# display_driver_rev_B.net
KiCad netlist of a schematic drawn in EAGLE
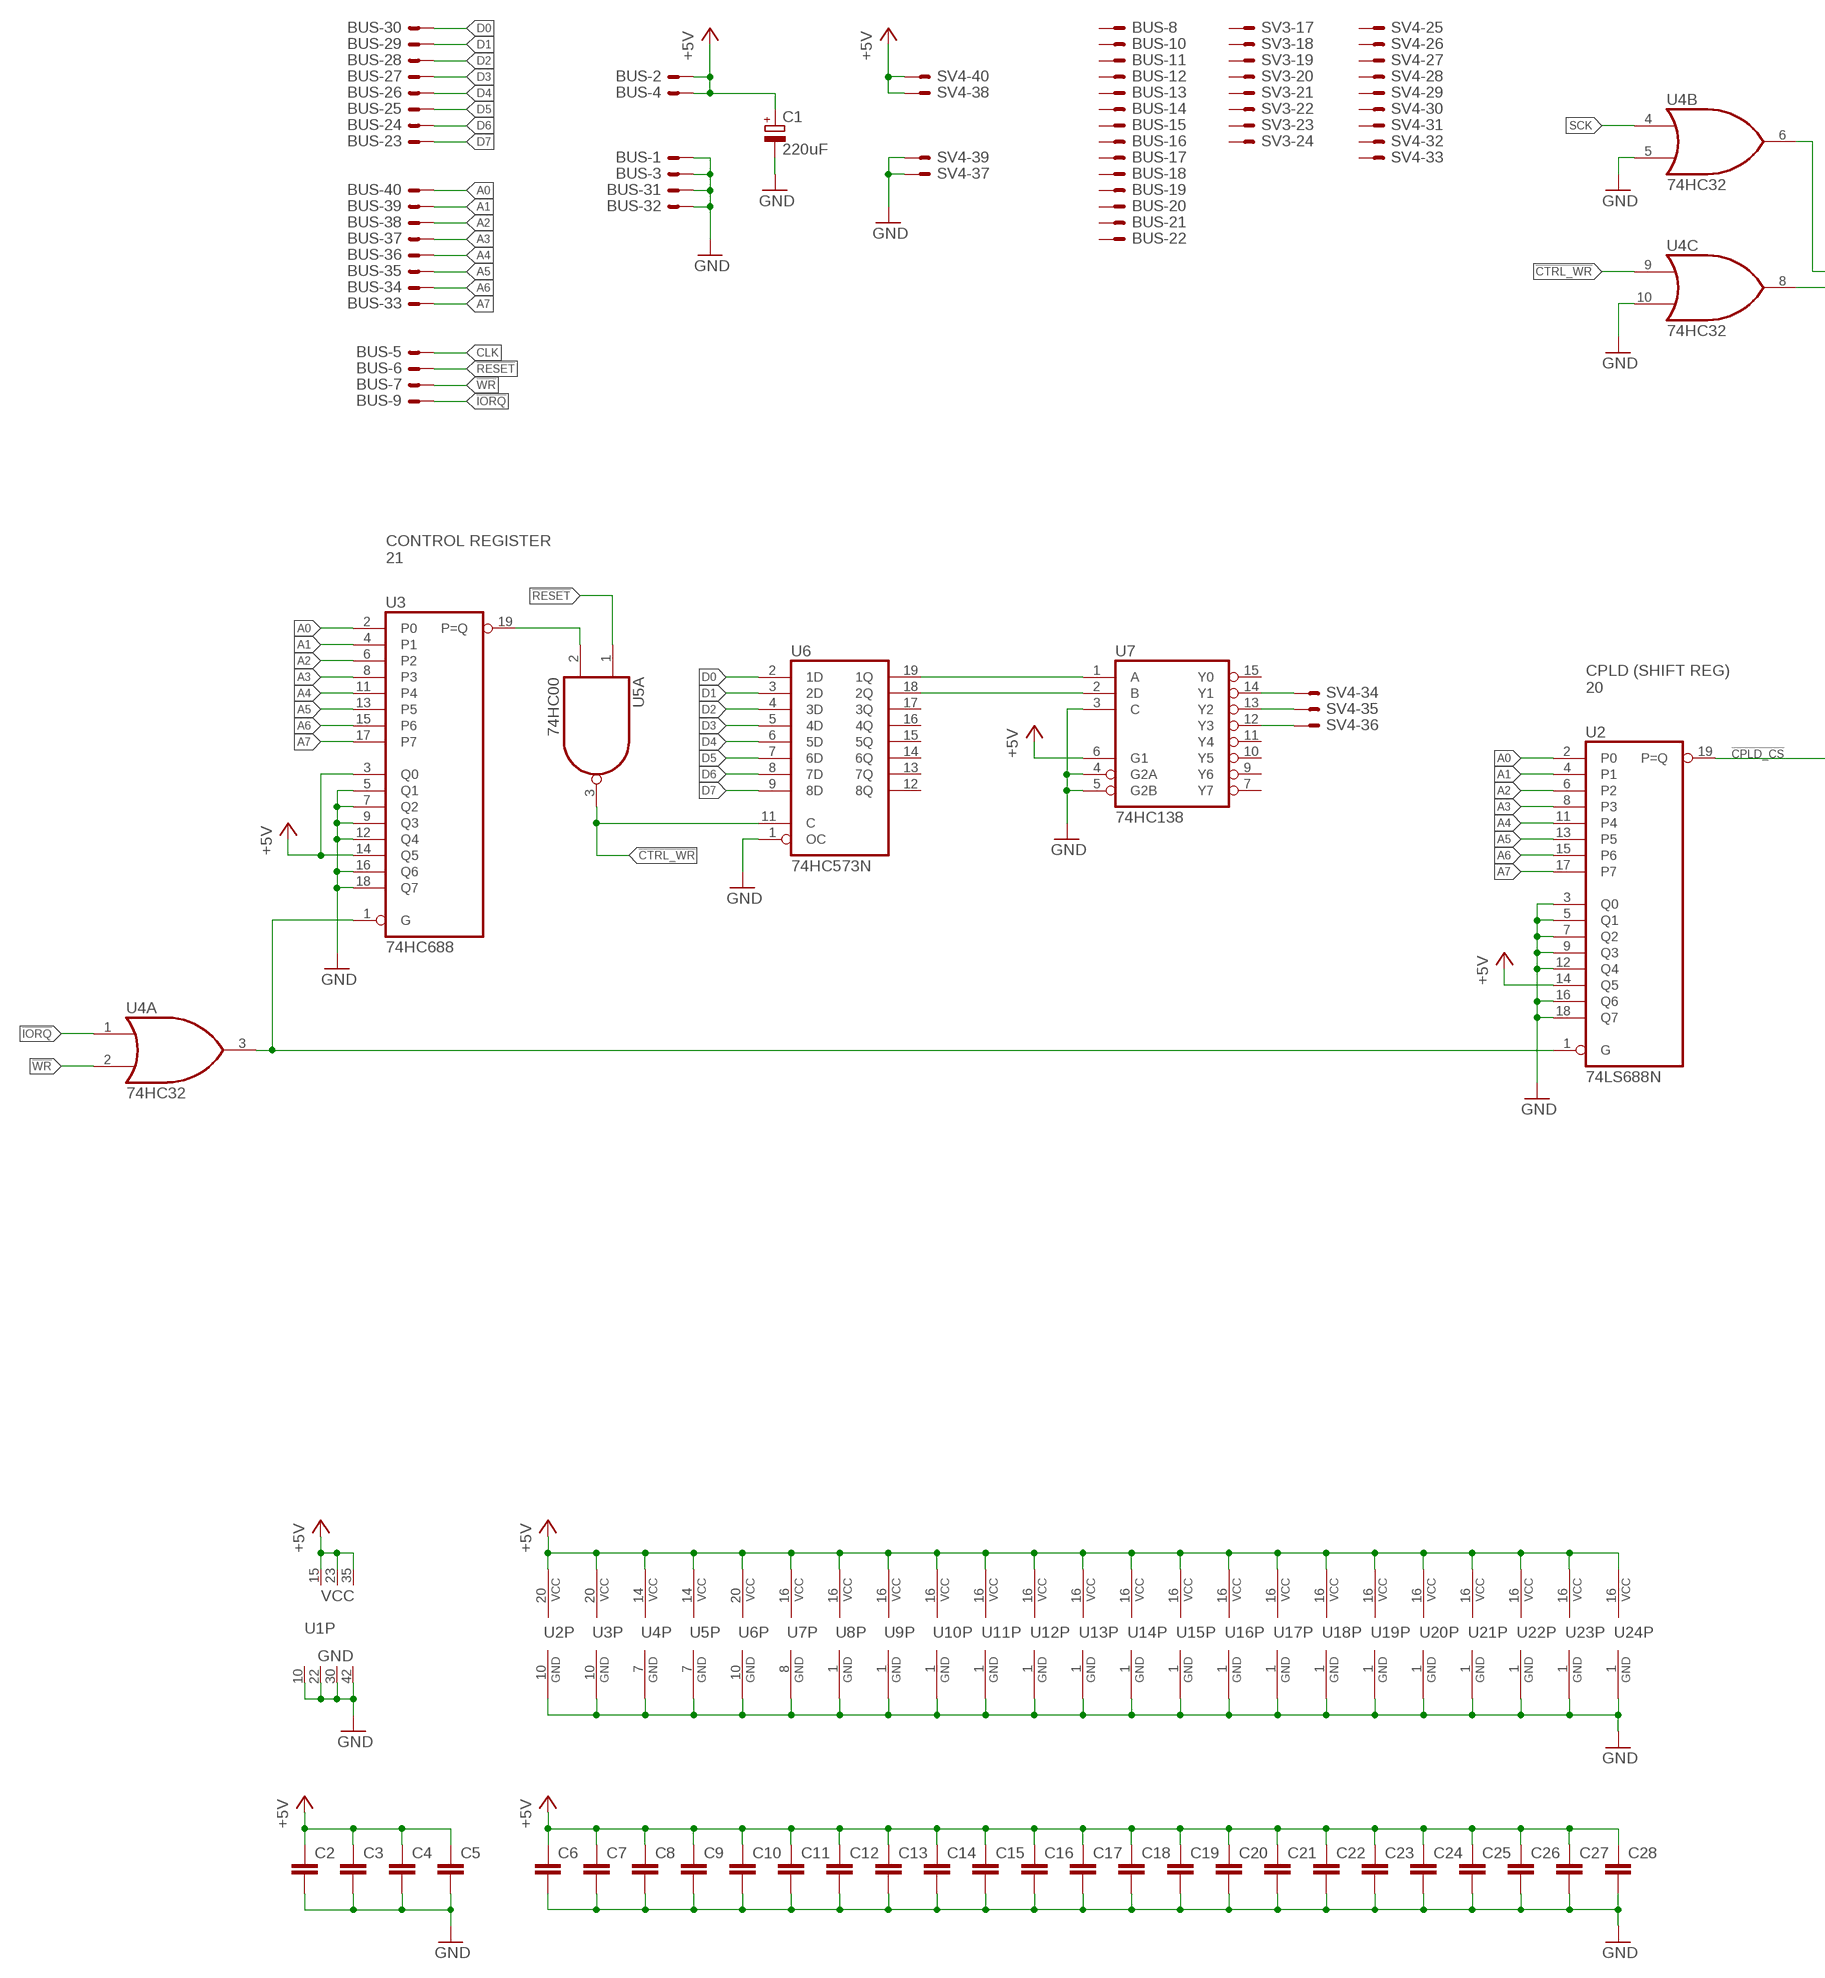
[diagram p0: schematic, sheet 1, part 1 of 2]
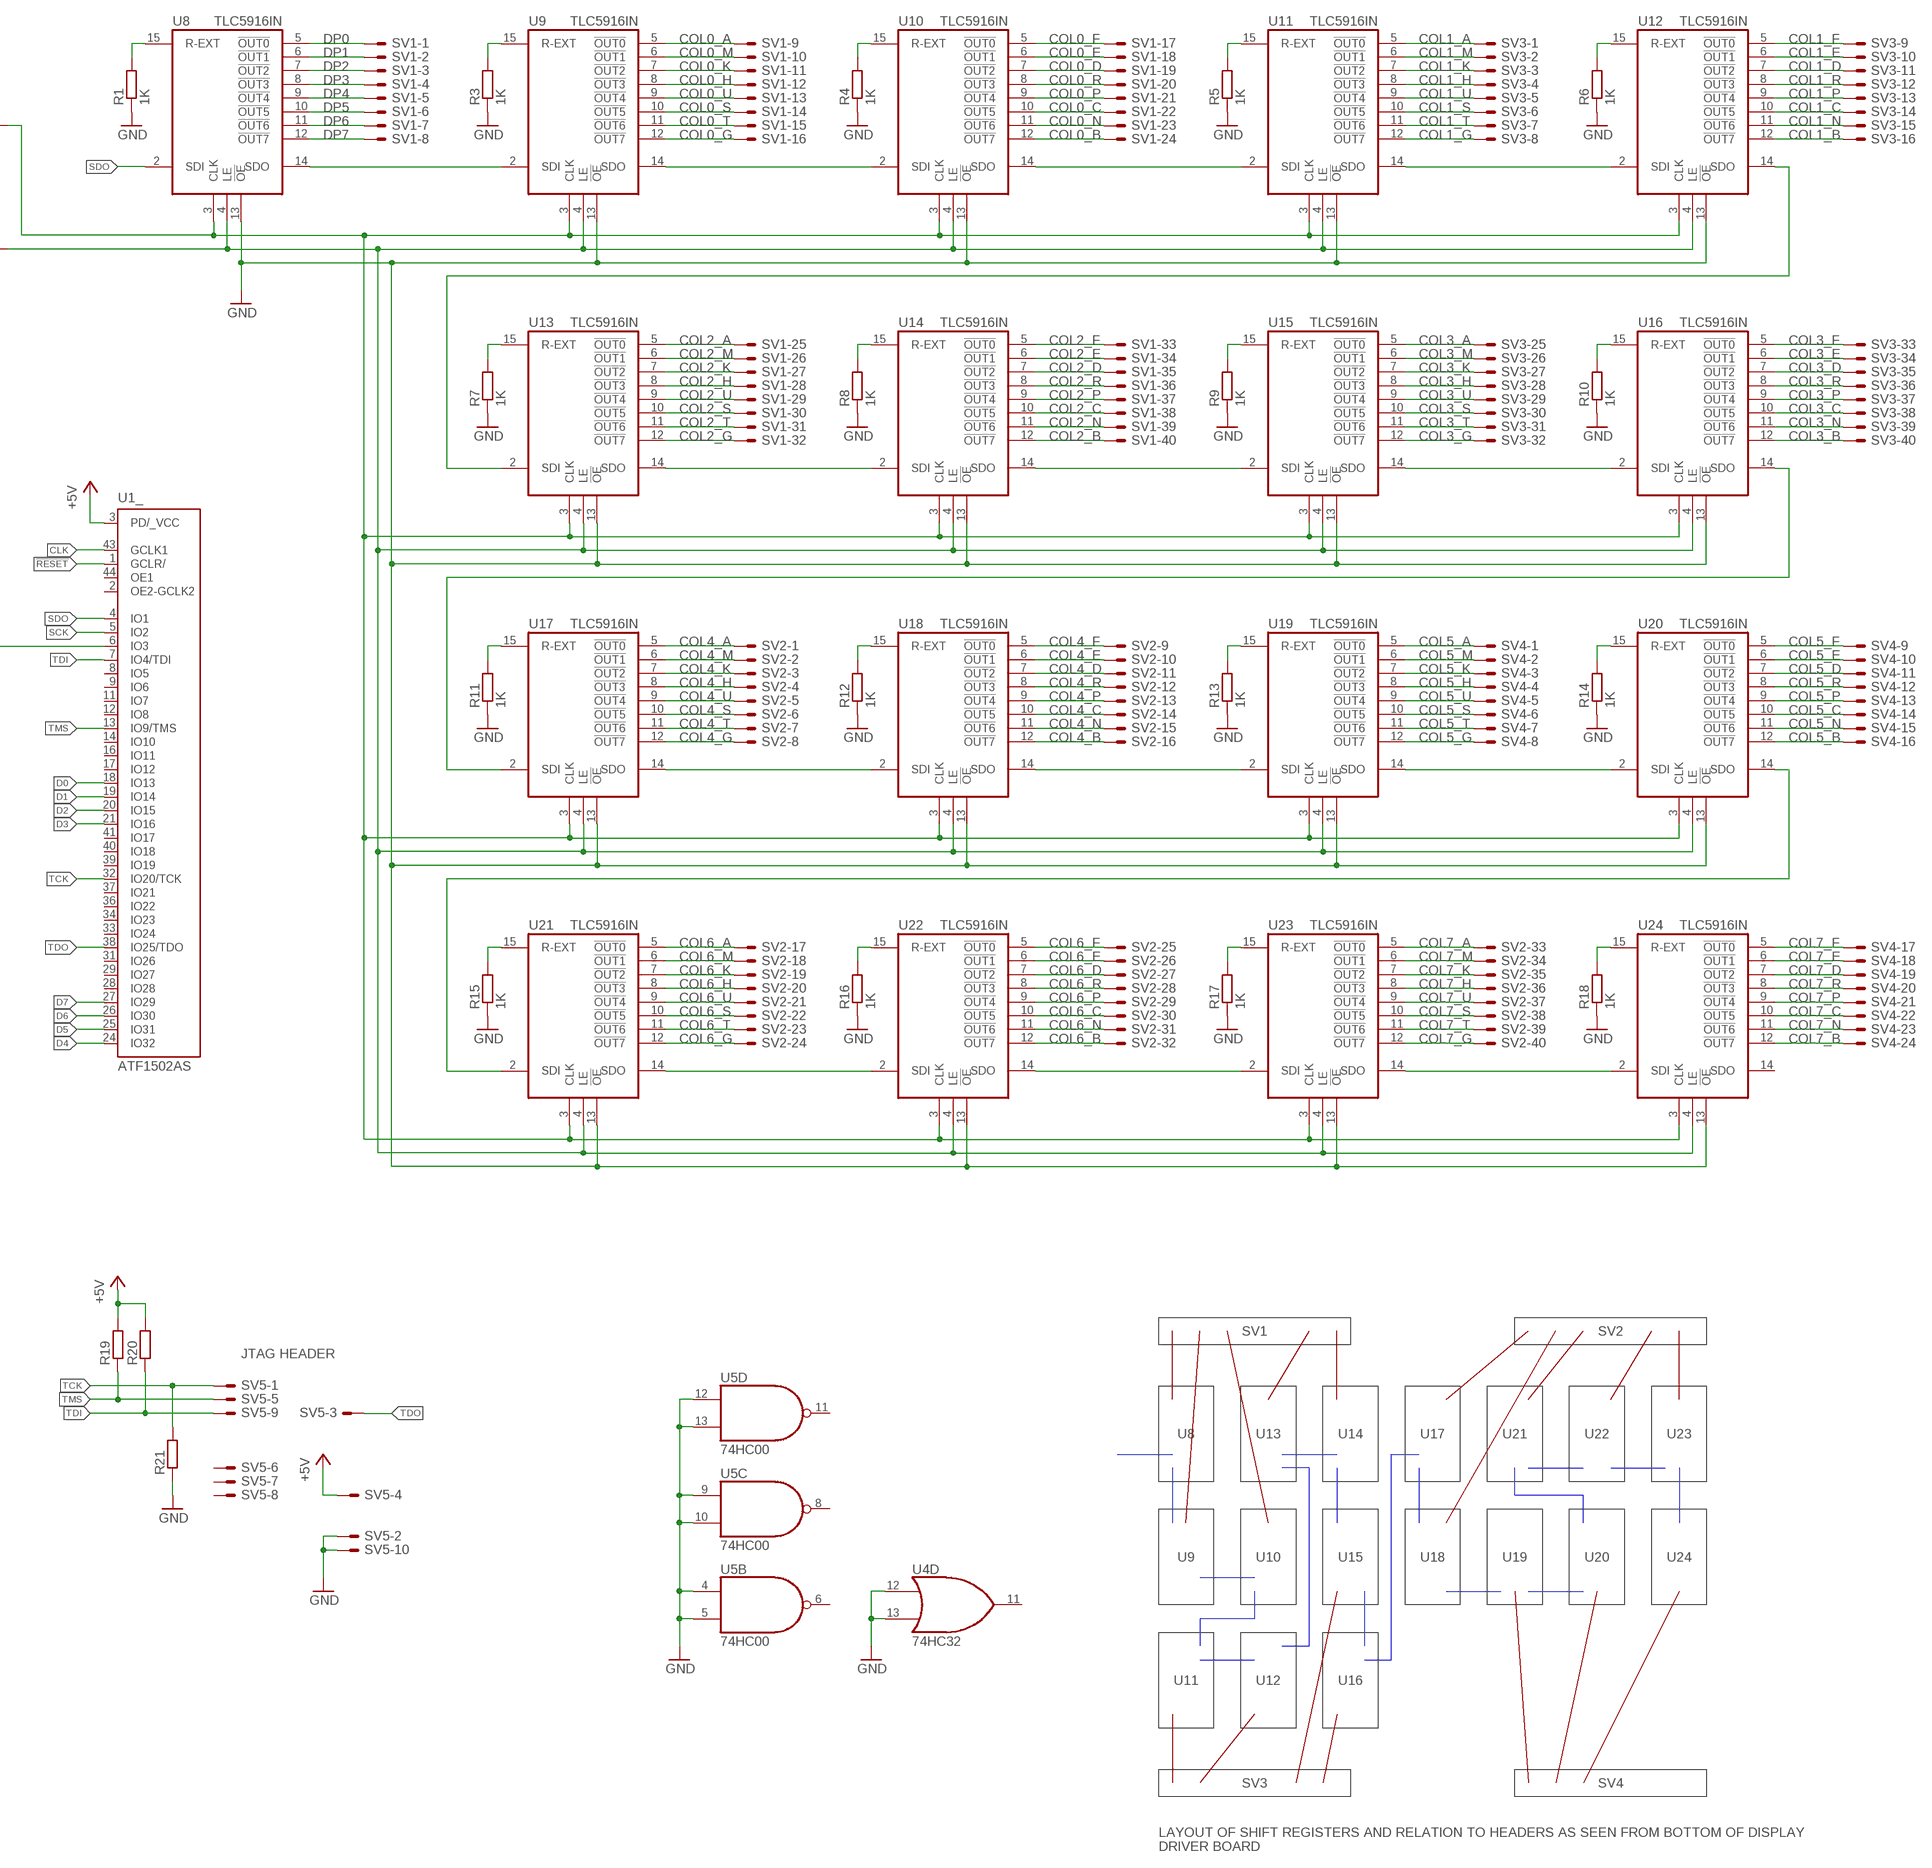
[diagram p1: schematic, sheet 1, part 2 of 2]

(export (version "E")
  (design (tool "Eeschema 10.0.6"))
  (components
    (comp (ref "BUS")
      (value "ML40E")
      (footprint "eagle-import:ML40")
      (libsource (lib "eagle-import") (part "ML40E"))
    )
    (comp (ref "C1")
      (value "220uF")
      (footprint "eagle-import:E3,5-8")
      (libsource (lib "eagle-import") (part "CPOL-EUE3.5-8"))
    )
    (comp (ref "C2")
      (value "C-EU050-025X075")
      (footprint "eagle-import:C050-025X075")
      (libsource (lib "eagle-import") (part "C-EU050-025X075"))
    )
    (comp (ref "C3")
      (value "C-EU050-025X075")
      (footprint "eagle-import:C050-025X075")
      (libsource (lib "eagle-import") (part "C-EU050-025X075"))
    )
    (comp (ref "C4")
      (value "C-EU050-025X075")
      (footprint "eagle-import:C050-025X075")
      (libsource (lib "eagle-import") (part "C-EU050-025X075"))
    )
    (comp (ref "C5")
      (value "C-EU050-025X075")
      (footprint "eagle-import:C050-025X075")
      (libsource (lib "eagle-import") (part "C-EU050-025X075"))
    )
    (comp (ref "C6")
      (value "C-EU050-025X075")
      (footprint "eagle-import:C050-025X075")
      (libsource (lib "eagle-import") (part "C-EU050-025X075"))
    )
    (comp (ref "C7")
      (value "C-EU050-025X075")
      (footprint "eagle-import:C050-025X075")
      (libsource (lib "eagle-import") (part "C-EU050-025X075"))
    )
    (comp (ref "C8")
      (value "C-EU050-025X075")
      (footprint "eagle-import:C050-025X075")
      (libsource (lib "eagle-import") (part "C-EU050-025X075"))
    )
    (comp (ref "C9")
      (value "C-EU050-025X075")
      (footprint "eagle-import:C050-025X075")
      (libsource (lib "eagle-import") (part "C-EU050-025X075"))
    )
    (comp (ref "C10")
      (value "C-EU050-025X075")
      (footprint "eagle-import:C050-025X075")
      (libsource (lib "eagle-import") (part "C-EU050-025X075"))
    )
    (comp (ref "C11")
      (value "C-EU050-025X075")
      (footprint "eagle-import:C050-025X075")
      (libsource (lib "eagle-import") (part "C-EU050-025X075"))
    )
    (comp (ref "C12")
      (value "C-EU050-025X075")
      (footprint "eagle-import:C050-025X075")
      (libsource (lib "eagle-import") (part "C-EU050-025X075"))
    )
    (comp (ref "C13")
      (value "C-EU050-025X075")
      (footprint "eagle-import:C050-025X075")
      (libsource (lib "eagle-import") (part "C-EU050-025X075"))
    )
    (comp (ref "C14")
      (value "C-EU050-025X075")
      (footprint "eagle-import:C050-025X075")
      (libsource (lib "eagle-import") (part "C-EU050-025X075"))
    )
    (comp (ref "C15")
      (value "C-EU050-025X075")
      (footprint "eagle-import:C050-025X075")
      (libsource (lib "eagle-import") (part "C-EU050-025X075"))
    )
    (comp (ref "C16")
      (value "C-EU050-025X075")
      (footprint "eagle-import:C050-025X075")
      (libsource (lib "eagle-import") (part "C-EU050-025X075"))
    )
    (comp (ref "C17")
      (value "C-EU050-025X075")
      (footprint "eagle-import:C050-025X075")
      (libsource (lib "eagle-import") (part "C-EU050-025X075"))
    )
    (comp (ref "C18")
      (value "C-EU050-025X075")
      (footprint "eagle-import:C050-025X075")
      (libsource (lib "eagle-import") (part "C-EU050-025X075"))
    )
    (comp (ref "C19")
      (value "C-EU050-025X075")
      (footprint "eagle-import:C050-025X075")
      (libsource (lib "eagle-import") (part "C-EU050-025X075"))
    )
    (comp (ref "C20")
      (value "C-EU050-025X075")
      (footprint "eagle-import:C050-025X075")
      (libsource (lib "eagle-import") (part "C-EU050-025X075"))
    )
    (comp (ref "C21")
      (value "C-EU050-025X075")
      (footprint "eagle-import:C050-025X075")
      (libsource (lib "eagle-import") (part "C-EU050-025X075"))
    )
    (comp (ref "C22")
      (value "C-EU050-025X075")
      (footprint "eagle-import:C050-025X075")
      (libsource (lib "eagle-import") (part "C-EU050-025X075"))
    )
    (comp (ref "C23")
      (value "C-EU050-025X075")
      (footprint "eagle-import:C050-025X075")
      (libsource (lib "eagle-import") (part "C-EU050-025X075"))
    )
    (comp (ref "C24")
      (value "C-EU050-025X075")
      (footprint "eagle-import:C050-025X075")
      (libsource (lib "eagle-import") (part "C-EU050-025X075"))
    )
    (comp (ref "C25")
      (value "C-EU050-025X075")
      (footprint "eagle-import:C050-025X075")
      (libsource (lib "eagle-import") (part "C-EU050-025X075"))
    )
    (comp (ref "C26")
      (value "C-EU050-025X075")
      (footprint "eagle-import:C050-025X075")
      (libsource (lib "eagle-import") (part "C-EU050-025X075"))
    )
    (comp (ref "C27")
      (value "C-EU050-025X075")
      (footprint "eagle-import:C050-025X075")
      (libsource (lib "eagle-import") (part "C-EU050-025X075"))
    )
    (comp (ref "C28")
      (value "C-EU050-025X075")
      (footprint "eagle-import:C050-025X075")
      (libsource (lib "eagle-import") (part "C-EU050-025X075"))
    )
    (comp (ref "R1")
      (value "1K")
      (footprint "eagle-import:0207_10")
      (libsource (lib "eagle-import") (part "R-EU_0207/10"))
    )
    (comp (ref "R3")
      (value "1K")
      (footprint "eagle-import:0207_10")
      (libsource (lib "eagle-import") (part "R-EU_0207/10"))
    )
    (comp (ref "R4")
      (value "1K")
      (footprint "eagle-import:0207_10")
      (libsource (lib "eagle-import") (part "R-EU_0207/10"))
    )
    (comp (ref "R5")
      (value "1K")
      (footprint "eagle-import:0207_10")
      (libsource (lib "eagle-import") (part "R-EU_0207/10"))
    )
    (comp (ref "R6")
      (value "1K")
      (footprint "eagle-import:0207_10")
      (libsource (lib "eagle-import") (part "R-EU_0207/10"))
    )
    (comp (ref "R7")
      (value "1K")
      (footprint "eagle-import:0207_10")
      (libsource (lib "eagle-import") (part "R-EU_0207/10"))
    )
    (comp (ref "R8")
      (value "1K")
      (footprint "eagle-import:0207_10")
      (libsource (lib "eagle-import") (part "R-EU_0207/10"))
    )
    (comp (ref "R9")
      (value "1K")
      (footprint "eagle-import:0207_10")
      (libsource (lib "eagle-import") (part "R-EU_0207/10"))
    )
    (comp (ref "R10")
      (value "1K")
      (footprint "eagle-import:0207_10")
      (libsource (lib "eagle-import") (part "R-EU_0207/10"))
    )
    (comp (ref "R11")
      (value "1K")
      (footprint "eagle-import:0207_10")
      (libsource (lib "eagle-import") (part "R-EU_0207/10"))
    )
    (comp (ref "R12")
      (value "1K")
      (footprint "eagle-import:0207_10")
      (libsource (lib "eagle-import") (part "R-EU_0207/10"))
    )
    (comp (ref "R13")
      (value "1K")
      (footprint "eagle-import:0207_10")
      (libsource (lib "eagle-import") (part "R-EU_0207/10"))
    )
    (comp (ref "R14")
      (value "1K")
      (footprint "eagle-import:0207_10")
      (libsource (lib "eagle-import") (part "R-EU_0207/10"))
    )
    (comp (ref "R15")
      (value "1K")
      (footprint "eagle-import:0207_10")
      (libsource (lib "eagle-import") (part "R-EU_0207/10"))
    )
    (comp (ref "R16")
      (value "1K")
      (footprint "eagle-import:0207_10")
      (libsource (lib "eagle-import") (part "R-EU_0207/10"))
    )
    (comp (ref "R17")
      (value "1K")
      (footprint "eagle-import:0207_10")
      (libsource (lib "eagle-import") (part "R-EU_0207/10"))
    )
    (comp (ref "R18")
      (value "1K")
      (footprint "eagle-import:0207_10")
      (libsource (lib "eagle-import") (part "R-EU_0207/10"))
    )
    (comp (ref "R19")
      (value "R-EU_0207/10")
      (footprint "eagle-import:0207_10")
      (libsource (lib "eagle-import") (part "R-EU_0207/10"))
    )
    (comp (ref "R20")
      (value "R-EU_0207/10")
      (footprint "eagle-import:0207_10")
      (libsource (lib "eagle-import") (part "R-EU_0207/10"))
    )
    (comp (ref "R21")
      (value "R-EU_0207/10")
      (footprint "eagle-import:0207_10")
      (libsource (lib "eagle-import") (part "R-EU_0207/10"))
    )
    (comp (ref "SV1")
      (value "ML40E")
      (footprint "eagle-import:ML40")
      (libsource (lib "eagle-import") (part "ML40E"))
    )
    (comp (ref "SV2")
      (value "ML40E")
      (footprint "eagle-import:ML40")
      (libsource (lib "eagle-import") (part "ML40E"))
    )
    (comp (ref "SV3")
      (value "ML40E")
      (footprint "eagle-import:ML40")
      (libsource (lib "eagle-import") (part "ML40E"))
    )
    (comp (ref "SV4")
      (value "ML40E")
      (footprint "eagle-import:ML40")
      (libsource (lib "eagle-import") (part "ML40E"))
    )
    (comp (ref "SV5")
      (value "ML10E")
      (footprint "eagle-import:ML10")
      (libsource (lib "eagle-import") (part "ML10E"))
    )
    (comp (ref "U1")
      (value "ATF1502AS")
      (footprint "eagle-import:PLCC-S44")
      (fields (field (name "MPN") "EPM7032SLC44-6N"))
      (libsource (lib "eagle-import") (part "EPM7032S44"))
    )
    (comp (ref "U2")
      (value "74LS688N")
      (footprint "eagle-import:DIL20")
      (libsource (lib "eagle-import") (part "74688NLS"))
    )
    (comp (ref "U3")
      (value "74HC688")
      (footprint "eagle-import:DIL20")
      (libsource (lib "eagle-import") (part "74688NLS"))
    )
    (comp (ref "U4")
      (value "74HC32")
      (footprint "eagle-import:DIL14")
      (libsource (lib "eagle-import") (part "7432NLS"))
    )
    (comp (ref "U5")
      (value "74HC00")
      (footprint "eagle-import:DIL14")
      (libsource (lib "eagle-import") (part "7400NLS"))
    )
    (comp (ref "U6")
      (value "74HC573N")
      (footprint "eagle-import:DIL20")
      (libsource (lib "eagle-import") (part "74573NHC"))
    )
    (comp (ref "U7")
      (value "74HC138")
      (footprint "eagle-import:DIL16")
      (libsource (lib "eagle-import") (part "74138NLS"))
    )
    (comp (ref "U8")
      (value "TLC5916IN")
      (footprint "eagle-import:DIL16")
      (libsource (lib "eagle-import") (part "TLC5916IN"))
    )
    (comp (ref "U9")
      (value "TLC5916IN")
      (footprint "eagle-import:DIL16")
      (libsource (lib "eagle-import") (part "TLC5916IN"))
    )
    (comp (ref "U10")
      (value "TLC5916IN")
      (footprint "eagle-import:DIL16")
      (libsource (lib "eagle-import") (part "TLC5916IN"))
    )
    (comp (ref "U11")
      (value "TLC5916IN")
      (footprint "eagle-import:DIL16")
      (libsource (lib "eagle-import") (part "TLC5916IN"))
    )
    (comp (ref "U12")
      (value "TLC5916IN")
      (footprint "eagle-import:DIL16")
      (libsource (lib "eagle-import") (part "TLC5916IN"))
    )
    (comp (ref "U13")
      (value "TLC5916IN")
      (footprint "eagle-import:DIL16")
      (libsource (lib "eagle-import") (part "TLC5916IN"))
    )
    (comp (ref "U14")
      (value "TLC5916IN")
      (footprint "eagle-import:DIL16")
      (libsource (lib "eagle-import") (part "TLC5916IN"))
    )
    (comp (ref "U15")
      (value "TLC5916IN")
      (footprint "eagle-import:DIL16")
      (libsource (lib "eagle-import") (part "TLC5916IN"))
    )
    (comp (ref "U16")
      (value "TLC5916IN")
      (footprint "eagle-import:DIL16")
      (libsource (lib "eagle-import") (part "TLC5916IN"))
    )
    (comp (ref "U17")
      (value "TLC5916IN")
      (footprint "eagle-import:DIL16")
      (libsource (lib "eagle-import") (part "TLC5916IN"))
    )
    (comp (ref "U18")
      (value "TLC5916IN")
      (footprint "eagle-import:DIL16")
      (libsource (lib "eagle-import") (part "TLC5916IN"))
    )
    (comp (ref "U19")
      (value "TLC5916IN")
      (footprint "eagle-import:DIL16")
      (libsource (lib "eagle-import") (part "TLC5916IN"))
    )
    (comp (ref "U20")
      (value "TLC5916IN")
      (footprint "eagle-import:DIL16")
      (libsource (lib "eagle-import") (part "TLC5916IN"))
    )
    (comp (ref "U21")
      (value "TLC5916IN")
      (footprint "eagle-import:DIL16")
      (libsource (lib "eagle-import") (part "TLC5916IN"))
    )
    (comp (ref "U22")
      (value "TLC5916IN")
      (footprint "eagle-import:DIL16")
      (libsource (lib "eagle-import") (part "TLC5916IN"))
    )
    (comp (ref "U23")
      (value "TLC5916IN")
      (footprint "eagle-import:DIL16")
      (libsource (lib "eagle-import") (part "TLC5916IN"))
    )
    (comp (ref "U24")
      (value "TLC5916IN")
      (footprint "eagle-import:DIL16")
      (libsource (lib "eagle-import") (part "TLC5916IN"))
    )
  )
  (nets
    (net (code "1") (name "+5V") (class "Default")
      (node (ref "BUS") (pin "2") (pinfunction "S_2") (pintype "passive"))
      (node (ref "BUS") (pin "4") (pinfunction "S_4") (pintype "passive"))
      (node (ref "C1") (pin "+") (pinfunction "+_+") (pintype "passive"))
      (node (ref "C10") (pin "1") (pinfunction "1_1") (pintype "passive"))
      (node (ref "C11") (pin "1") (pinfunction "1_1") (pintype "passive"))
      (node (ref "C12") (pin "1") (pinfunction "1_1") (pintype "passive"))
      (node (ref "C13") (pin "1") (pinfunction "1_1") (pintype "passive"))
      (node (ref "C14") (pin "1") (pinfunction "1_1") (pintype "passive"))
      (node (ref "C15") (pin "1") (pinfunction "1_1") (pintype "passive"))
      (node (ref "C16") (pin "1") (pinfunction "1_1") (pintype "passive"))
      (node (ref "C17") (pin "1") (pinfunction "1_1") (pintype "passive"))
      (node (ref "C18") (pin "1") (pinfunction "1_1") (pintype "passive"))
      (node (ref "C19") (pin "1") (pinfunction "1_1") (pintype "passive"))
      (node (ref "C2") (pin "1") (pinfunction "1_1") (pintype "passive"))
      (node (ref "C20") (pin "1") (pinfunction "1_1") (pintype "passive"))
      (node (ref "C21") (pin "1") (pinfunction "1_1") (pintype "passive"))
      (node (ref "C22") (pin "1") (pinfunction "1_1") (pintype "passive"))
      (node (ref "C23") (pin "1") (pinfunction "1_1") (pintype "passive"))
      (node (ref "C24") (pin "1") (pinfunction "1_1") (pintype "passive"))
      (node (ref "C25") (pin "1") (pinfunction "1_1") (pintype "passive"))
      (node (ref "C26") (pin "1") (pinfunction "1_1") (pintype "passive"))
      (node (ref "C27") (pin "1") (pinfunction "1_1") (pintype "passive"))
      (node (ref "C28") (pin "1") (pinfunction "1_1") (pintype "passive"))
      (node (ref "C3") (pin "1") (pinfunction "1_1") (pintype "passive"))
      (node (ref "C4") (pin "1") (pinfunction "1_1") (pintype "passive"))
      (node (ref "C5") (pin "1") (pinfunction "1_1") (pintype "passive"))
      (node (ref "C6") (pin "1") (pinfunction "1_1") (pintype "passive"))
      (node (ref "C7") (pin "1") (pinfunction "1_1") (pintype "passive"))
      (node (ref "C8") (pin "1") (pinfunction "1_1") (pintype "passive"))
      (node (ref "C9") (pin "1") (pinfunction "1_1") (pintype "passive"))
      (node (ref "R19") (pin "2") (pinfunction "2_2") (pintype "passive"))
      (node (ref "R20") (pin "2") (pinfunction "2_2") (pintype "passive"))
      (node (ref "SV4") (pin "38") (pinfunction "S_38") (pintype "passive"))
      (node (ref "SV4") (pin "40") (pinfunction "S_40") (pintype "passive"))
      (node (ref "SV5") (pin "4") (pinfunction "S_4") (pintype "passive"))
      (node (ref "U1") (pin "15") (pinfunction "VCC_15") (pintype "power_in"))
      (node (ref "U1") (pin "23") (pinfunction "VCC_23") (pintype "power_in"))
      (node (ref "U1") (pin "3") (pinfunction "PD/_VCC_3") (pintype "passive"))
      (node (ref "U1") (pin "35") (pinfunction "VCC_35") (pintype "power_in"))
      (node (ref "U10") (pin "16") (pinfunction "VCC_16") (pintype "power_in"))
      (node (ref "U11") (pin "16") (pinfunction "VCC_16") (pintype "power_in"))
      (node (ref "U12") (pin "16") (pinfunction "VCC_16") (pintype "power_in"))
      (node (ref "U13") (pin "16") (pinfunction "VCC_16") (pintype "power_in"))
      (node (ref "U14") (pin "16") (pinfunction "VCC_16") (pintype "power_in"))
      (node (ref "U15") (pin "16") (pinfunction "VCC_16") (pintype "power_in"))
      (node (ref "U16") (pin "16") (pinfunction "VCC_16") (pintype "power_in"))
      (node (ref "U17") (pin "16") (pinfunction "VCC_16") (pintype "power_in"))
      (node (ref "U18") (pin "16") (pinfunction "VCC_16") (pintype "power_in"))
      (node (ref "U19") (pin "16") (pinfunction "VCC_16") (pintype "power_in"))
      (node (ref "U2") (pin "14") (pinfunction "Q5_14") (pintype "input"))
      (node (ref "U2") (pin "20") (pinfunction "VCC_20") (pintype "power_in"))
      (node (ref "U20") (pin "16") (pinfunction "VCC_16") (pintype "power_in"))
      (node (ref "U21") (pin "16") (pinfunction "VCC_16") (pintype "power_in"))
      (node (ref "U22") (pin "16") (pinfunction "VCC_16") (pintype "power_in"))
      (node (ref "U23") (pin "16") (pinfunction "VCC_16") (pintype "power_in"))
      (node (ref "U24") (pin "16") (pinfunction "VCC_16") (pintype "power_in"))
      (node (ref "U3") (pin "14") (pinfunction "Q5_14") (pintype "input"))
      (node (ref "U3") (pin "20") (pinfunction "VCC_20") (pintype "power_in"))
      (node (ref "U3") (pin "3") (pinfunction "Q0_3") (pintype "input"))
      (node (ref "U4") (pin "14") (pinfunction "VCC_14") (pintype "power_in"))
      (node (ref "U5") (pin "14") (pinfunction "VCC_14") (pintype "power_in"))
      (node (ref "U6") (pin "20") (pinfunction "VCC_20") (pintype "power_in"))
      (node (ref "U7") (pin "16") (pinfunction "VCC_16") (pintype "power_in"))
      (node (ref "U7") (pin "6") (pinfunction "G1_6") (pintype "input"))
      (node (ref "U8") (pin "16") (pinfunction "VCC_16") (pintype "power_in"))
      (node (ref "U9") (pin "16") (pinfunction "VCC_16") (pintype "power_in"))
    )
    (net (code "2") (name "/COL0_A") (class "Default")
      (node (ref "SV1") (pin "9") (pinfunction "S_9") (pintype "passive"))
      (node (ref "U9") (pin "5") (pinfunction "~{OUT0}_5") (pintype "open_collector"))
    )
    (net (code "3") (name "/COL0_B") (class "Default")
      (node (ref "SV1") (pin "24") (pinfunction "S_24") (pintype "passive"))
      (node (ref "U10") (pin "12") (pinfunction "~{OUT7}_12") (pintype "open_collector"))
    )
    (net (code "4") (name "/COL0_C") (class "Default")
      (node (ref "SV1") (pin "22") (pinfunction "S_22") (pintype "passive"))
      (node (ref "U10") (pin "10") (pinfunction "~{OUT5}_10") (pintype "open_collector"))
    )
    (net (code "5") (name "/COL0_D") (class "Default")
      (node (ref "SV1") (pin "19") (pinfunction "S_19") (pintype "passive"))
      (node (ref "U10") (pin "7") (pinfunction "~{OUT2}_7") (pintype "open_collector"))
    )
    (net (code "6") (name "/COL0_E") (class "Default")
      (node (ref "SV1") (pin "18") (pinfunction "S_18") (pintype "passive"))
      (node (ref "U10") (pin "6") (pinfunction "~{OUT1}_6") (pintype "open_collector"))
    )
    (net (code "7") (name "/COL0_F") (class "Default")
      (node (ref "SV1") (pin "17") (pinfunction "S_17") (pintype "passive"))
      (node (ref "U10") (pin "5") (pinfunction "~{OUT0}_5") (pintype "open_collector"))
    )
    (net (code "8") (name "/COL0_G") (class "Default")
      (node (ref "SV1") (pin "16") (pinfunction "S_16") (pintype "passive"))
      (node (ref "U9") (pin "12") (pinfunction "~{OUT7}_12") (pintype "open_collector"))
    )
    (net (code "9") (name "/COL0_H") (class "Default")
      (node (ref "SV1") (pin "12") (pinfunction "S_12") (pintype "passive"))
      (node (ref "U9") (pin "8") (pinfunction "~{OUT3}_8") (pintype "open_collector"))
    )
    (net (code "10") (name "/COL0_K") (class "Default")
      (node (ref "SV1") (pin "11") (pinfunction "S_11") (pintype "passive"))
      (node (ref "U9") (pin "7") (pinfunction "~{OUT2}_7") (pintype "open_collector"))
    )
    (net (code "11") (name "/COL0_M") (class "Default")
      (node (ref "SV1") (pin "10") (pinfunction "S_10") (pintype "passive"))
      (node (ref "U9") (pin "6") (pinfunction "~{OUT1}_6") (pintype "open_collector"))
    )
    (net (code "12") (name "/COL0_N") (class "Default")
      (node (ref "SV1") (pin "23") (pinfunction "S_23") (pintype "passive"))
      (node (ref "U10") (pin "11") (pinfunction "~{OUT6}_11") (pintype "open_collector"))
    )
    (net (code "13") (name "/COL0_P") (class "Default")
      (node (ref "SV1") (pin "21") (pinfunction "S_21") (pintype "passive"))
      (node (ref "U10") (pin "9") (pinfunction "~{OUT4}_9") (pintype "open_collector"))
    )
    (net (code "14") (name "/COL0_R") (class "Default")
      (node (ref "SV1") (pin "20") (pinfunction "S_20") (pintype "passive"))
      (node (ref "U10") (pin "8") (pinfunction "~{OUT3}_8") (pintype "open_collector"))
    )
    (net (code "15") (name "/COL0_S") (class "Default")
      (node (ref "SV1") (pin "14") (pinfunction "S_14") (pintype "passive"))
      (node (ref "U9") (pin "10") (pinfunction "~{OUT5}_10") (pintype "open_collector"))
    )
    (net (code "16") (name "/COL0_T") (class "Default")
      (node (ref "SV1") (pin "15") (pinfunction "S_15") (pintype "passive"))
      (node (ref "U9") (pin "11") (pinfunction "~{OUT6}_11") (pintype "open_collector"))
    )
    (net (code "17") (name "/COL0_U") (class "Default")
      (node (ref "SV1") (pin "13") (pinfunction "S_13") (pintype "passive"))
      (node (ref "U9") (pin "9") (pinfunction "~{OUT4}_9") (pintype "open_collector"))
    )
    (net (code "18") (name "/COL1_A") (class "Default")
      (node (ref "SV3") (pin "1") (pinfunction "S_1") (pintype "passive"))
      (node (ref "U11") (pin "5") (pinfunction "~{OUT0}_5") (pintype "open_collector"))
    )
    (net (code "19") (name "/COL1_B") (class "Default")
      (node (ref "SV3") (pin "16") (pinfunction "S_16") (pintype "passive"))
      (node (ref "U12") (pin "12") (pinfunction "~{OUT7}_12") (pintype "open_collector"))
    )
    (net (code "20") (name "/COL1_C") (class "Default")
      (node (ref "SV3") (pin "14") (pinfunction "S_14") (pintype "passive"))
      (node (ref "U12") (pin "10") (pinfunction "~{OUT5}_10") (pintype "open_collector"))
    )
    (net (code "21") (name "/COL1_D") (class "Default")
      (node (ref "SV3") (pin "11") (pinfunction "S_11") (pintype "passive"))
      (node (ref "U12") (pin "7") (pinfunction "~{OUT2}_7") (pintype "open_collector"))
    )
    (net (code "22") (name "/COL1_E") (class "Default")
      (node (ref "SV3") (pin "10") (pinfunction "S_10") (pintype "passive"))
      (node (ref "U12") (pin "6") (pinfunction "~{OUT1}_6") (pintype "open_collector"))
    )
    (net (code "23") (name "/COL1_F") (class "Default")
      (node (ref "SV3") (pin "9") (pinfunction "S_9") (pintype "passive"))
      (node (ref "U12") (pin "5") (pinfunction "~{OUT0}_5") (pintype "open_collector"))
    )
    (net (code "24") (name "/COL1_G") (class "Default")
      (node (ref "SV3") (pin "8") (pinfunction "S_8") (pintype "passive"))
      (node (ref "U11") (pin "12") (pinfunction "~{OUT7}_12") (pintype "open_collector"))
    )
    (net (code "25") (name "/COL1_H") (class "Default")
      (node (ref "SV3") (pin "4") (pinfunction "S_4") (pintype "passive"))
      (node (ref "U11") (pin "8") (pinfunction "~{OUT3}_8") (pintype "open_collector"))
    )
    (net (code "26") (name "/COL1_K") (class "Default")
      (node (ref "SV3") (pin "3") (pinfunction "S_3") (pintype "passive"))
      (node (ref "U11") (pin "7") (pinfunction "~{OUT2}_7") (pintype "open_collector"))
    )
    (net (code "27") (name "/COL1_M") (class "Default")
      (node (ref "SV3") (pin "2") (pinfunction "S_2") (pintype "passive"))
      (node (ref "U11") (pin "6") (pinfunction "~{OUT1}_6") (pintype "open_collector"))
    )
    (net (code "28") (name "/COL1_N") (class "Default")
      (node (ref "SV3") (pin "15") (pinfunction "S_15") (pintype "passive"))
      (node (ref "U12") (pin "11") (pinfunction "~{OUT6}_11") (pintype "open_collector"))
    )
    (net (code "29") (name "/COL1_P") (class "Default")
      (node (ref "SV3") (pin "13") (pinfunction "S_13") (pintype "passive"))
      (node (ref "U12") (pin "9") (pinfunction "~{OUT4}_9") (pintype "open_collector"))
    )
    (net (code "30") (name "/COL1_R") (class "Default")
      (node (ref "SV3") (pin "12") (pinfunction "S_12") (pintype "passive"))
      (node (ref "U12") (pin "8") (pinfunction "~{OUT3}_8") (pintype "open_collector"))
    )
    (net (code "31") (name "/COL1_S") (class "Default")
      (node (ref "SV3") (pin "6") (pinfunction "S_6") (pintype "passive"))
      (node (ref "U11") (pin "10") (pinfunction "~{OUT5}_10") (pintype "open_collector"))
    )
    (net (code "32") (name "/COL1_T") (class "Default")
      (node (ref "SV3") (pin "7") (pinfunction "S_7") (pintype "passive"))
      (node (ref "U11") (pin "11") (pinfunction "~{OUT6}_11") (pintype "open_collector"))
    )
    (net (code "33") (name "/COL1_U") (class "Default")
      (node (ref "SV3") (pin "5") (pinfunction "S_5") (pintype "passive"))
      (node (ref "U11") (pin "9") (pinfunction "~{OUT4}_9") (pintype "open_collector"))
    )
    (net (code "34") (name "/COL2_A") (class "Default")
      (node (ref "SV1") (pin "25") (pinfunction "S_25") (pintype "passive"))
      (node (ref "U13") (pin "5") (pinfunction "~{OUT0}_5") (pintype "open_collector"))
    )
    (net (code "35") (name "/COL2_B") (class "Default")
      (node (ref "SV1") (pin "40") (pinfunction "S_40") (pintype "passive"))
      (node (ref "U14") (pin "12") (pinfunction "~{OUT7}_12") (pintype "open_collector"))
    )
    (net (code "36") (name "/COL2_C") (class "Default")
      (node (ref "SV1") (pin "38") (pinfunction "S_38") (pintype "passive"))
      (node (ref "U14") (pin "10") (pinfunction "~{OUT5}_10") (pintype "open_collector"))
    )
    (net (code "37") (name "/COL2_D") (class "Default")
      (node (ref "SV1") (pin "35") (pinfunction "S_35") (pintype "passive"))
      (node (ref "U14") (pin "7") (pinfunction "~{OUT2}_7") (pintype "open_collector"))
    )
    (net (code "38") (name "/COL2_E") (class "Default")
      (node (ref "SV1") (pin "34") (pinfunction "S_34") (pintype "passive"))
      (node (ref "U14") (pin "6") (pinfunction "~{OUT1}_6") (pintype "open_collector"))
    )
    (net (code "39") (name "/COL2_F") (class "Default")
      (node (ref "SV1") (pin "33") (pinfunction "S_33") (pintype "passive"))
      (node (ref "U14") (pin "5") (pinfunction "~{OUT0}_5") (pintype "open_collector"))
    )
    (net (code "40") (name "/COL2_G") (class "Default")
      (node (ref "SV1") (pin "32") (pinfunction "S_32") (pintype "passive"))
      (node (ref "U13") (pin "12") (pinfunction "~{OUT7}_12") (pintype "open_collector"))
    )
    (net (code "41") (name "/COL2_H") (class "Default")
      (node (ref "SV1") (pin "28") (pinfunction "S_28") (pintype "passive"))
      (node (ref "U13") (pin "8") (pinfunction "~{OUT3}_8") (pintype "open_collector"))
    )
    (net (code "42") (name "/COL2_K") (class "Default")
      (node (ref "SV1") (pin "27") (pinfunction "S_27") (pintype "passive"))
      (node (ref "U13") (pin "7") (pinfunction "~{OUT2}_7") (pintype "open_collector"))
    )
    (net (code "43") (name "/COL2_M") (class "Default")
      (node (ref "SV1") (pin "26") (pinfunction "S_26") (pintype "passive"))
      (node (ref "U13") (pin "6") (pinfunction "~{OUT1}_6") (pintype "open_collector"))
    )
    (net (code "44") (name "/COL2_N") (class "Default")
      (node (ref "SV1") (pin "39") (pinfunction "S_39") (pintype "passive"))
      (node (ref "U14") (pin "11") (pinfunction "~{OUT6}_11") (pintype "open_collector"))
    )
    (net (code "45") (name "/COL2_P") (class "Default")
      (node (ref "SV1") (pin "37") (pinfunction "S_37") (pintype "passive"))
      (node (ref "U14") (pin "9") (pinfunction "~{OUT4}_9") (pintype "open_collector"))
    )
    (net (code "46") (name "/COL2_R") (class "Default")
      (node (ref "SV1") (pin "36") (pinfunction "S_36") (pintype "passive"))
      (node (ref "U14") (pin "8") (pinfunction "~{OUT3}_8") (pintype "open_collector"))
    )
    (net (code "47") (name "/COL2_S") (class "Default")
      (node (ref "SV1") (pin "30") (pinfunction "S_30") (pintype "passive"))
      (node (ref "U13") (pin "10") (pinfunction "~{OUT5}_10") (pintype "open_collector"))
    )
    (net (code "48") (name "/COL2_T") (class "Default")
      (node (ref "SV1") (pin "31") (pinfunction "S_31") (pintype "passive"))
      (node (ref "U13") (pin "11") (pinfunction "~{OUT6}_11") (pintype "open_collector"))
    )
    (net (code "49") (name "/COL2_U") (class "Default")
      (node (ref "SV1") (pin "29") (pinfunction "S_29") (pintype "passive"))
      (node (ref "U13") (pin "9") (pinfunction "~{OUT4}_9") (pintype "open_collector"))
    )
    (net (code "50") (name "/COL3_A") (class "Default")
      (node (ref "SV3") (pin "25") (pinfunction "S_25") (pintype "passive"))
      (node (ref "U15") (pin "5") (pinfunction "~{OUT0}_5") (pintype "open_collector"))
    )
    (net (code "51") (name "/COL3_B") (class "Default")
      (node (ref "SV3") (pin "40") (pinfunction "S_40") (pintype "passive"))
      (node (ref "U16") (pin "12") (pinfunction "~{OUT7}_12") (pintype "open_collector"))
    )
    (net (code "52") (name "/COL3_C") (class "Default")
      (node (ref "SV3") (pin "38") (pinfunction "S_38") (pintype "passive"))
      (node (ref "U16") (pin "10") (pinfunction "~{OUT5}_10") (pintype "open_collector"))
    )
    (net (code "53") (name "/COL3_D") (class "Default")
      (node (ref "SV3") (pin "35") (pinfunction "S_35") (pintype "passive"))
      (node (ref "U16") (pin "7") (pinfunction "~{OUT2}_7") (pintype "open_collector"))
    )
    (net (code "54") (name "/COL3_E") (class "Default")
      (node (ref "SV3") (pin "34") (pinfunction "S_34") (pintype "passive"))
      (node (ref "U16") (pin "6") (pinfunction "~{OUT1}_6") (pintype "open_collector"))
    )
    (net (code "55") (name "/COL3_F") (class "Default")
      (node (ref "SV3") (pin "33") (pinfunction "S_33") (pintype "passive"))
      (node (ref "U16") (pin "5") (pinfunction "~{OUT0}_5") (pintype "open_collector"))
    )
    (net (code "56") (name "/COL3_G") (class "Default")
      (node (ref "SV3") (pin "32") (pinfunction "S_32") (pintype "passive"))
      (node (ref "U15") (pin "12") (pinfunction "~{OUT7}_12") (pintype "open_collector"))
    )
    (net (code "57") (name "/COL3_H") (class "Default")
      (node (ref "SV3") (pin "28") (pinfunction "S_28") (pintype "passive"))
      (node (ref "U15") (pin "8") (pinfunction "~{OUT3}_8") (pintype "open_collector"))
    )
    (net (code "58") (name "/COL3_K") (class "Default")
      (node (ref "SV3") (pin "27") (pinfunction "S_27") (pintype "passive"))
      (node (ref "U15") (pin "7") (pinfunction "~{OUT2}_7") (pintype "open_collector"))
    )
    (net (code "59") (name "/COL3_M") (class "Default")
      (node (ref "SV3") (pin "26") (pinfunction "S_26") (pintype "passive"))
      (node (ref "U15") (pin "6") (pinfunction "~{OUT1}_6") (pintype "open_collector"))
    )
    (net (code "60") (name "/COL3_N") (class "Default")
      (node (ref "SV3") (pin "39") (pinfunction "S_39") (pintype "passive"))
      (node (ref "U16") (pin "11") (pinfunction "~{OUT6}_11") (pintype "open_collector"))
    )
    (net (code "61") (name "/COL3_P") (class "Default")
      (node (ref "SV3") (pin "37") (pinfunction "S_37") (pintype "passive"))
      (node (ref "U16") (pin "9") (pinfunction "~{OUT4}_9") (pintype "open_collector"))
    )
    (net (code "62") (name "/COL3_R") (class "Default")
      (node (ref "SV3") (pin "36") (pinfunction "S_36") (pintype "passive"))
      (node (ref "U16") (pin "8") (pinfunction "~{OUT3}_8") (pintype "open_collector"))
    )
    (net (code "63") (name "/COL3_S") (class "Default")
      (node (ref "SV3") (pin "30") (pinfunction "S_30") (pintype "passive"))
      (node (ref "U15") (pin "10") (pinfunction "~{OUT5}_10") (pintype "open_collector"))
    )
    (net (code "64") (name "/COL3_T") (class "Default")
      (node (ref "SV3") (pin "31") (pinfunction "S_31") (pintype "passive"))
      (node (ref "U15") (pin "11") (pinfunction "~{OUT6}_11") (pintype "open_collector"))
    )
    (net (code "65") (name "/COL3_U") (class "Default")
      (node (ref "SV3") (pin "29") (pinfunction "S_29") (pintype "passive"))
      (node (ref "U15") (pin "9") (pinfunction "~{OUT4}_9") (pintype "open_collector"))
    )
    (net (code "66") (name "/COL4_A") (class "Default")
      (node (ref "SV2") (pin "1") (pinfunction "S_1") (pintype "passive"))
      (node (ref "U17") (pin "5") (pinfunction "~{OUT0}_5") (pintype "open_collector"))
    )
    (net (code "67") (name "/COL4_B") (class "Default")
      (node (ref "SV2") (pin "16") (pinfunction "S_16") (pintype "passive"))
      (node (ref "U18") (pin "12") (pinfunction "~{OUT7}_12") (pintype "open_collector"))
    )
    (net (code "68") (name "/COL4_C") (class "Default")
      (node (ref "SV2") (pin "14") (pinfunction "S_14") (pintype "passive"))
      (node (ref "U18") (pin "10") (pinfunction "~{OUT5}_10") (pintype "open_collector"))
    )
    (net (code "69") (name "/COL4_D") (class "Default")
      (node (ref "SV2") (pin "11") (pinfunction "S_11") (pintype "passive"))
      (node (ref "U18") (pin "7") (pinfunction "~{OUT2}_7") (pintype "open_collector"))
    )
    (net (code "70") (name "/COL4_E") (class "Default")
      (node (ref "SV2") (pin "10") (pinfunction "S_10") (pintype "passive"))
      (node (ref "U18") (pin "6") (pinfunction "~{OUT1}_6") (pintype "open_collector"))
    )
    (net (code "71") (name "/COL4_F") (class "Default")
      (node (ref "SV2") (pin "9") (pinfunction "S_9") (pintype "passive"))
      (node (ref "U18") (pin "5") (pinfunction "~{OUT0}_5") (pintype "open_collector"))
    )
    (net (code "72") (name "/COL4_G") (class "Default")
      (node (ref "SV2") (pin "8") (pinfunction "S_8") (pintype "passive"))
      (node (ref "U17") (pin "12") (pinfunction "~{OUT7}_12") (pintype "open_collector"))
    )
    (net (code "73") (name "/COL4_H") (class "Default")
      (node (ref "SV2") (pin "4") (pinfunction "S_4") (pintype "passive"))
      (node (ref "U17") (pin "8") (pinfunction "~{OUT3}_8") (pintype "open_collector"))
    )
    (net (code "74") (name "/COL4_K") (class "Default")
      (node (ref "SV2") (pin "3") (pinfunction "S_3") (pintype "passive"))
      (node (ref "U17") (pin "7") (pinfunction "~{OUT2}_7") (pintype "open_collector"))
    )
    (net (code "75") (name "/COL4_M") (class "Default")
      (node (ref "SV2") (pin "2") (pinfunction "S_2") (pintype "passive"))
      (node (ref "U17") (pin "6") (pinfunction "~{OUT1}_6") (pintype "open_collector"))
    )
    (net (code "76") (name "/COL4_N") (class "Default")
      (node (ref "SV2") (pin "15") (pinfunction "S_15") (pintype "passive"))
      (node (ref "U18") (pin "11") (pinfunction "~{OUT6}_11") (pintype "open_collector"))
    )
    (net (code "77") (name "/COL4_P") (class "Default")
      (node (ref "SV2") (pin "13") (pinfunction "S_13") (pintype "passive"))
      (node (ref "U18") (pin "9") (pinfunction "~{OUT4}_9") (pintype "open_collector"))
    )
    (net (code "78") (name "/COL4_R") (class "Default")
      (node (ref "SV2") (pin "12") (pinfunction "S_12") (pintype "passive"))
      (node (ref "U18") (pin "8") (pinfunction "~{OUT3}_8") (pintype "open_collector"))
    )
    (net (code "79") (name "/COL4_S") (class "Default")
      (node (ref "SV2") (pin "6") (pinfunction "S_6") (pintype "passive"))
      (node (ref "U17") (pin "10") (pinfunction "~{OUT5}_10") (pintype "open_collector"))
    )
    (net (code "80") (name "/COL4_T") (class "Default")
      (node (ref "SV2") (pin "7") (pinfunction "S_7") (pintype "passive"))
      (node (ref "U17") (pin "11") (pinfunction "~{OUT6}_11") (pintype "open_collector"))
    )
    (net (code "81") (name "/COL4_U") (class "Default")
      (node (ref "SV2") (pin "5") (pinfunction "S_5") (pintype "passive"))
      (node (ref "U17") (pin "9") (pinfunction "~{OUT4}_9") (pintype "open_collector"))
    )
    (net (code "82") (name "/COL5_A") (class "Default")
      (node (ref "SV4") (pin "1") (pinfunction "S_1") (pintype "passive"))
      (node (ref "U19") (pin "5") (pinfunction "~{OUT0}_5") (pintype "open_collector"))
    )
    (net (code "83") (name "/COL5_B") (class "Default")
      (node (ref "SV4") (pin "16") (pinfunction "S_16") (pintype "passive"))
      (node (ref "U20") (pin "12") (pinfunction "~{OUT7}_12") (pintype "open_collector"))
    )
    (net (code "84") (name "/COL5_C") (class "Default")
      (node (ref "SV4") (pin "14") (pinfunction "S_14") (pintype "passive"))
      (node (ref "U20") (pin "10") (pinfunction "~{OUT5}_10") (pintype "open_collector"))
    )
    (net (code "85") (name "/COL5_D") (class "Default")
      (node (ref "SV4") (pin "11") (pinfunction "S_11") (pintype "passive"))
      (node (ref "U20") (pin "7") (pinfunction "~{OUT2}_7") (pintype "open_collector"))
    )
    (net (code "86") (name "/COL5_E") (class "Default")
      (node (ref "SV4") (pin "10") (pinfunction "S_10") (pintype "passive"))
      (node (ref "U20") (pin "6") (pinfunction "~{OUT1}_6") (pintype "open_collector"))
    )
    (net (code "87") (name "/COL5_F") (class "Default")
      (node (ref "SV4") (pin "9") (pinfunction "S_9") (pintype "passive"))
      (node (ref "U20") (pin "5") (pinfunction "~{OUT0}_5") (pintype "open_collector"))
    )
    (net (code "88") (name "/COL5_G") (class "Default")
      (node (ref "SV4") (pin "8") (pinfunction "S_8") (pintype "passive"))
      (node (ref "U19") (pin "12") (pinfunction "~{OUT7}_12") (pintype "open_collector"))
    )
    (net (code "89") (name "/COL5_H") (class "Default")
      (node (ref "SV4") (pin "4") (pinfunction "S_4") (pintype "passive"))
      (node (ref "U19") (pin "8") (pinfunction "~{OUT3}_8") (pintype "open_collector"))
    )
    (net (code "90") (name "/COL5_K") (class "Default")
      (node (ref "SV4") (pin "3") (pinfunction "S_3") (pintype "passive"))
      (node (ref "U19") (pin "7") (pinfunction "~{OUT2}_7") (pintype "open_collector"))
    )
    (net (code "91") (name "/COL5_M") (class "Default")
      (node (ref "SV4") (pin "2") (pinfunction "S_2") (pintype "passive"))
      (node (ref "U19") (pin "6") (pinfunction "~{OUT1}_6") (pintype "open_collector"))
    )
    (net (code "92") (name "/COL5_N") (class "Default")
      (node (ref "SV4") (pin "15") (pinfunction "S_15") (pintype "passive"))
      (node (ref "U20") (pin "11") (pinfunction "~{OUT6}_11") (pintype "open_collector"))
    )
    (net (code "93") (name "/COL5_P") (class "Default")
      (node (ref "SV4") (pin "13") (pinfunction "S_13") (pintype "passive"))
      (node (ref "U20") (pin "9") (pinfunction "~{OUT4}_9") (pintype "open_collector"))
    )
    (net (code "94") (name "/COL5_R") (class "Default")
      (node (ref "SV4") (pin "12") (pinfunction "S_12") (pintype "passive"))
      (node (ref "U20") (pin "8") (pinfunction "~{OUT3}_8") (pintype "open_collector"))
    )
    (net (code "95") (name "/COL5_S") (class "Default")
      (node (ref "SV4") (pin "6") (pinfunction "S_6") (pintype "passive"))
      (node (ref "U19") (pin "10") (pinfunction "~{OUT5}_10") (pintype "open_collector"))
    )
    (net (code "96") (name "/COL5_T") (class "Default")
      (node (ref "SV4") (pin "7") (pinfunction "S_7") (pintype "passive"))
      (node (ref "U19") (pin "11") (pinfunction "~{OUT6}_11") (pintype "open_collector"))
    )
    (net (code "97") (name "/COL5_U") (class "Default")
      (node (ref "SV4") (pin "5") (pinfunction "S_5") (pintype "passive"))
      (node (ref "U19") (pin "9") (pinfunction "~{OUT4}_9") (pintype "open_collector"))
    )
    (net (code "98") (name "/COL6_A") (class "Default")
      (node (ref "SV2") (pin "17") (pinfunction "S_17") (pintype "passive"))
      (node (ref "U21") (pin "5") (pinfunction "~{OUT0}_5") (pintype "open_collector"))
    )
    (net (code "99") (name "/COL6_B") (class "Default")
      (node (ref "SV2") (pin "32") (pinfunction "S_32") (pintype "passive"))
      (node (ref "U22") (pin "12") (pinfunction "~{OUT7}_12") (pintype "open_collector"))
    )
    (net (code "100") (name "/COL6_C") (class "Default")
      (node (ref "SV2") (pin "30") (pinfunction "S_30") (pintype "passive"))
      (node (ref "U22") (pin "10") (pinfunction "~{OUT5}_10") (pintype "open_collector"))
    )
    (net (code "101") (name "/COL6_D") (class "Default")
      (node (ref "SV2") (pin "27") (pinfunction "S_27") (pintype "passive"))
      (node (ref "U22") (pin "7") (pinfunction "~{OUT2}_7") (pintype "open_collector"))
    )
    (net (code "102") (name "/COL6_E") (class "Default")
      (node (ref "SV2") (pin "26") (pinfunction "S_26") (pintype "passive"))
      (node (ref "U22") (pin "6") (pinfunction "~{OUT1}_6") (pintype "open_collector"))
    )
    (net (code "103") (name "/COL6_F") (class "Default")
      (node (ref "SV2") (pin "25") (pinfunction "S_25") (pintype "passive"))
      (node (ref "U22") (pin "5") (pinfunction "~{OUT0}_5") (pintype "open_collector"))
    )
    (net (code "104") (name "/COL6_G") (class "Default")
      (node (ref "SV2") (pin "24") (pinfunction "S_24") (pintype "passive"))
      (node (ref "U21") (pin "12") (pinfunction "~{OUT7}_12") (pintype "open_collector"))
    )
    (net (code "105") (name "/COL6_H") (class "Default")
      (node (ref "SV2") (pin "20") (pinfunction "S_20") (pintype "passive"))
      (node (ref "U21") (pin "8") (pinfunction "~{OUT3}_8") (pintype "open_collector"))
    )
    (net (code "106") (name "/COL6_K") (class "Default")
      (node (ref "SV2") (pin "19") (pinfunction "S_19") (pintype "passive"))
      (node (ref "U21") (pin "7") (pinfunction "~{OUT2}_7") (pintype "open_collector"))
    )
    (net (code "107") (name "/COL6_M") (class "Default")
      (node (ref "SV2") (pin "18") (pinfunction "S_18") (pintype "passive"))
      (node (ref "U21") (pin "6") (pinfunction "~{OUT1}_6") (pintype "open_collector"))
    )
    (net (code "108") (name "/COL6_N") (class "Default")
      (node (ref "SV2") (pin "31") (pinfunction "S_31") (pintype "passive"))
      (node (ref "U22") (pin "11") (pinfunction "~{OUT6}_11") (pintype "open_collector"))
    )
    (net (code "109") (name "/COL6_P") (class "Default")
      (node (ref "SV2") (pin "29") (pinfunction "S_29") (pintype "passive"))
      (node (ref "U22") (pin "9") (pinfunction "~{OUT4}_9") (pintype "open_collector"))
    )
    (net (code "110") (name "/COL6_R") (class "Default")
      (node (ref "SV2") (pin "28") (pinfunction "S_28") (pintype "passive"))
      (node (ref "U22") (pin "8") (pinfunction "~{OUT3}_8") (pintype "open_collector"))
    )
    (net (code "111") (name "/COL6_S") (class "Default")
      (node (ref "SV2") (pin "22") (pinfunction "S_22") (pintype "passive"))
      (node (ref "U21") (pin "10") (pinfunction "~{OUT5}_10") (pintype "open_collector"))
    )
    (net (code "112") (name "/COL6_T") (class "Default")
      (node (ref "SV2") (pin "23") (pinfunction "S_23") (pintype "passive"))
      (node (ref "U21") (pin "11") (pinfunction "~{OUT6}_11") (pintype "open_collector"))
    )
    (net (code "113") (name "/COL6_U") (class "Default")
      (node (ref "SV2") (pin "21") (pinfunction "S_21") (pintype "passive"))
      (node (ref "U21") (pin "9") (pinfunction "~{OUT4}_9") (pintype "open_collector"))
    )
    (net (code "114") (name "/COL7_A") (class "Default")
      (node (ref "SV2") (pin "33") (pinfunction "S_33") (pintype "passive"))
      (node (ref "U23") (pin "5") (pinfunction "~{OUT0}_5") (pintype "open_collector"))
    )
    (net (code "115") (name "/COL7_B") (class "Default")
      (node (ref "SV4") (pin "24") (pinfunction "S_24") (pintype "passive"))
      (node (ref "U24") (pin "12") (pinfunction "~{OUT7}_12") (pintype "open_collector"))
    )
    (net (code "116") (name "/COL7_C") (class "Default")
      (node (ref "SV4") (pin "22") (pinfunction "S_22") (pintype "passive"))
      (node (ref "U24") (pin "10") (pinfunction "~{OUT5}_10") (pintype "open_collector"))
    )
    (net (code "117") (name "/COL7_D") (class "Default")
      (node (ref "SV4") (pin "19") (pinfunction "S_19") (pintype "passive"))
      (node (ref "U24") (pin "7") (pinfunction "~{OUT2}_7") (pintype "open_collector"))
    )
    (net (code "118") (name "/COL7_E") (class "Default")
      (node (ref "SV4") (pin "18") (pinfunction "S_18") (pintype "passive"))
      (node (ref "U24") (pin "6") (pinfunction "~{OUT1}_6") (pintype "open_collector"))
    )
    (net (code "119") (name "/COL7_F") (class "Default")
      (node (ref "SV4") (pin "17") (pinfunction "S_17") (pintype "passive"))
      (node (ref "U24") (pin "5") (pinfunction "~{OUT0}_5") (pintype "open_collector"))
    )
    (net (code "120") (name "/COL7_G") (class "Default")
      (node (ref "SV2") (pin "40") (pinfunction "S_40") (pintype "passive"))
      (node (ref "U23") (pin "12") (pinfunction "~{OUT7}_12") (pintype "open_collector"))
    )
    (net (code "121") (name "/COL7_H") (class "Default")
      (node (ref "SV2") (pin "36") (pinfunction "S_36") (pintype "passive"))
      (node (ref "U23") (pin "8") (pinfunction "~{OUT3}_8") (pintype "open_collector"))
    )
    (net (code "122") (name "/COL7_K") (class "Default")
      (node (ref "SV2") (pin "35") (pinfunction "S_35") (pintype "passive"))
      (node (ref "U23") (pin "7") (pinfunction "~{OUT2}_7") (pintype "open_collector"))
    )
    (net (code "123") (name "/COL7_M") (class "Default")
      (node (ref "SV2") (pin "34") (pinfunction "S_34") (pintype "passive"))
      (node (ref "U23") (pin "6") (pinfunction "~{OUT1}_6") (pintype "open_collector"))
    )
    (net (code "124") (name "/COL7_N") (class "Default")
      (node (ref "SV4") (pin "23") (pinfunction "S_23") (pintype "passive"))
      (node (ref "U24") (pin "11") (pinfunction "~{OUT6}_11") (pintype "open_collector"))
    )
    (net (code "125") (name "/COL7_P") (class "Default")
      (node (ref "SV4") (pin "21") (pinfunction "S_21") (pintype "passive"))
      (node (ref "U24") (pin "9") (pinfunction "~{OUT4}_9") (pintype "open_collector"))
    )
    (net (code "126") (name "/COL7_R") (class "Default")
      (node (ref "SV4") (pin "20") (pinfunction "S_20") (pintype "passive"))
      (node (ref "U24") (pin "8") (pinfunction "~{OUT3}_8") (pintype "open_collector"))
    )
    (net (code "127") (name "/COL7_S") (class "Default")
      (node (ref "SV2") (pin "38") (pinfunction "S_38") (pintype "passive"))
      (node (ref "U23") (pin "10") (pinfunction "~{OUT5}_10") (pintype "open_collector"))
    )
    (net (code "128") (name "/COL7_T") (class "Default")
      (node (ref "SV2") (pin "39") (pinfunction "S_39") (pintype "passive"))
      (node (ref "U23") (pin "11") (pinfunction "~{OUT6}_11") (pintype "open_collector"))
    )
    (net (code "129") (name "/COL7_U") (class "Default")
      (node (ref "SV2") (pin "37") (pinfunction "S_37") (pintype "passive"))
      (node (ref "U23") (pin "9") (pinfunction "~{OUT4}_9") (pintype "open_collector"))
    )
    (net (code "130") (name "/DP0") (class "Default")
      (node (ref "SV1") (pin "1") (pinfunction "S_1") (pintype "passive"))
      (node (ref "U8") (pin "5") (pinfunction "~{OUT0}_5") (pintype "open_collector"))
    )
    (net (code "131") (name "/DP1") (class "Default")
      (node (ref "SV1") (pin "2") (pinfunction "S_2") (pintype "passive"))
      (node (ref "U8") (pin "6") (pinfunction "~{OUT1}_6") (pintype "open_collector"))
    )
    (net (code "132") (name "/DP2") (class "Default")
      (node (ref "SV1") (pin "3") (pinfunction "S_3") (pintype "passive"))
      (node (ref "U8") (pin "7") (pinfunction "~{OUT2}_7") (pintype "open_collector"))
    )
    (net (code "133") (name "/DP3") (class "Default")
      (node (ref "SV1") (pin "4") (pinfunction "S_4") (pintype "passive"))
      (node (ref "U8") (pin "8") (pinfunction "~{OUT3}_8") (pintype "open_collector"))
    )
    (net (code "134") (name "/DP4") (class "Default")
      (node (ref "SV1") (pin "5") (pinfunction "S_5") (pintype "passive"))
      (node (ref "U8") (pin "9") (pinfunction "~{OUT4}_9") (pintype "open_collector"))
    )
    (net (code "135") (name "/DP5") (class "Default")
      (node (ref "SV1") (pin "6") (pinfunction "S_6") (pintype "passive"))
      (node (ref "U8") (pin "10") (pinfunction "~{OUT5}_10") (pintype "open_collector"))
    )
    (net (code "136") (name "/DP6") (class "Default")
      (node (ref "SV1") (pin "7") (pinfunction "S_7") (pintype "passive"))
      (node (ref "U8") (pin "11") (pinfunction "~{OUT6}_11") (pintype "open_collector"))
    )
    (net (code "137") (name "/DP7") (class "Default")
      (node (ref "SV1") (pin "8") (pinfunction "S_8") (pintype "passive"))
      (node (ref "U8") (pin "12") (pinfunction "~{OUT7}_12") (pintype "open_collector"))
    )
    (net (code "138") (name "/N$1") (class "Default")
      (node (ref "U10") (pin "3") (pinfunction "CLK_3") (pintype "input"))
      (node (ref "U11") (pin "3") (pinfunction "CLK_3") (pintype "input"))
      (node (ref "U12") (pin "3") (pinfunction "CLK_3") (pintype "input"))
      (node (ref "U13") (pin "3") (pinfunction "CLK_3") (pintype "input"))
      (node (ref "U14") (pin "3") (pinfunction "CLK_3") (pintype "input"))
      (node (ref "U15") (pin "3") (pinfunction "CLK_3") (pintype "input"))
      (node (ref "U16") (pin "3") (pinfunction "CLK_3") (pintype "input"))
      (node (ref "U17") (pin "3") (pinfunction "CLK_3") (pintype "input"))
      (node (ref "U18") (pin "3") (pinfunction "CLK_3") (pintype "input"))
      (node (ref "U19") (pin "3") (pinfunction "CLK_3") (pintype "input"))
      (node (ref "U20") (pin "3") (pinfunction "CLK_3") (pintype "input"))
      (node (ref "U21") (pin "3") (pinfunction "CLK_3") (pintype "input"))
      (node (ref "U22") (pin "3") (pinfunction "CLK_3") (pintype "input"))
      (node (ref "U23") (pin "3") (pinfunction "CLK_3") (pintype "input"))
      (node (ref "U24") (pin "3") (pinfunction "CLK_3") (pintype "input"))
      (node (ref "U3") (pin "19") (pinfunction "P=Q_19") (pintype "output"))
      (node (ref "U4") (pin "6") (pinfunction "O_6") (pintype "output"))
      (node (ref "U5") (pin "2") (pinfunction "I1_2") (pintype "input"))
      (node (ref "U8") (pin "3") (pinfunction "CLK_3") (pintype "input"))
      (node (ref "U9") (pin "3") (pinfunction "CLK_3") (pintype "input"))
    )
    (net (code "139") (name "/~{CPLD_CS}") (class "Default")
      (node (ref "U1") (pin "6") (pinfunction "IO3_6") (pintype "bidirectional"))
      (node (ref "U2") (pin "19") (pinfunction "P=Q_19") (pintype "output"))
    )
    (net (code "140") (name "/~{CTRL_WR}") (class "Default")
      (node (ref "U4") (pin "9") (pinfunction "I0_9") (pintype "input"))
      (node (ref "U5") (pin "3") (pinfunction "O_3") (pintype "output"))
      (node (ref "U6") (pin "11") (pinfunction "C_11") (pintype "input"))
    )
    (net (code "141") (name "/~{IORQ}") (class "Default")
      (node (ref "BUS") (pin "9") (pinfunction "S_9") (pintype "passive"))
      (node (ref "U4") (pin "1") (pinfunction "I0_1") (pintype "input"))
    )
    (net (code "142") (name "/~{RESET}") (class "Default")
      (node (ref "BUS") (pin "6") (pinfunction "S_6") (pintype "passive"))
      (node (ref "U1") (pin "1") (pinfunction "GCLR/_1") (pintype "input"))
      (node (ref "U5") (pin "1") (pinfunction "I0_1") (pintype "input"))
    )
    (net (code "143") (name "/~{WR}") (class "Default")
      (node (ref "BUS") (pin "7") (pinfunction "S_7") (pintype "passive"))
      (node (ref "U4") (pin "2") (pinfunction "I1_2") (pintype "input"))
    )
    (net (code "144") (name "A0") (class "Default")
      (node (ref "BUS") (pin "40") (pinfunction "S_40") (pintype "passive"))
      (node (ref "U2") (pin "2") (pinfunction "P0_2") (pintype "input"))
      (node (ref "U3") (pin "2") (pinfunction "P0_2") (pintype "input"))
    )
    (net (code "145") (name "A1") (class "Default")
      (node (ref "BUS") (pin "39") (pinfunction "S_39") (pintype "passive"))
      (node (ref "U2") (pin "4") (pinfunction "P1_4") (pintype "input"))
      (node (ref "U3") (pin "4") (pinfunction "P1_4") (pintype "input"))
    )
    (net (code "146") (name "A2") (class "Default")
      (node (ref "BUS") (pin "38") (pinfunction "S_38") (pintype "passive"))
      (node (ref "U2") (pin "6") (pinfunction "P2_6") (pintype "input"))
      (node (ref "U3") (pin "6") (pinfunction "P2_6") (pintype "input"))
    )
    (net (code "147") (name "A3") (class "Default")
      (node (ref "BUS") (pin "37") (pinfunction "S_37") (pintype "passive"))
      (node (ref "U2") (pin "8") (pinfunction "P3_8") (pintype "input"))
      (node (ref "U3") (pin "8") (pinfunction "P3_8") (pintype "input"))
    )
    (net (code "148") (name "A4") (class "Default")
      (node (ref "BUS") (pin "36") (pinfunction "S_36") (pintype "passive"))
      (node (ref "U2") (pin "11") (pinfunction "P4_11") (pintype "input"))
      (node (ref "U3") (pin "11") (pinfunction "P4_11") (pintype "input"))
    )
    (net (code "149") (name "A5") (class "Default")
      (node (ref "BUS") (pin "35") (pinfunction "S_35") (pintype "passive"))
      (node (ref "U2") (pin "13") (pinfunction "P5_13") (pintype "input"))
      (node (ref "U3") (pin "13") (pinfunction "P5_13") (pintype "input"))
    )
    (net (code "150") (name "A6") (class "Default")
      (node (ref "BUS") (pin "34") (pinfunction "S_34") (pintype "passive"))
      (node (ref "U2") (pin "15") (pinfunction "P6_15") (pintype "input"))
      (node (ref "U3") (pin "15") (pinfunction "P6_15") (pintype "input"))
    )
    (net (code "151") (name "A7") (class "Default")
      (node (ref "BUS") (pin "33") (pinfunction "S_33") (pintype "passive"))
      (node (ref "U2") (pin "17") (pinfunction "P7_17") (pintype "input"))
      (node (ref "U3") (pin "17") (pinfunction "P7_17") (pintype "input"))
    )
    (net (code "152") (name "CLK") (class "Default")
      (node (ref "BUS") (pin "5") (pinfunction "S_5") (pintype "passive"))
      (node (ref "U1") (pin "43") (pinfunction "GCLK1_43") (pintype "input"))
    )
    (net (code "153") (name "D0") (class "Default")
      (node (ref "BUS") (pin "30") (pinfunction "S_30") (pintype "passive"))
      (node (ref "U1") (pin "18") (pinfunction "IO13_18") (pintype "bidirectional"))
      (node (ref "U6") (pin "2") (pinfunction "1D_2") (pintype "input"))
    )
    (net (code "154") (name "D1") (class "Default")
      (node (ref "BUS") (pin "29") (pinfunction "S_29") (pintype "passive"))
      (node (ref "U1") (pin "19") (pinfunction "IO14_19") (pintype "bidirectional"))
      (node (ref "U6") (pin "3") (pinfunction "2D_3") (pintype "input"))
    )
    (net (code "155") (name "D2") (class "Default")
      (node (ref "BUS") (pin "28") (pinfunction "S_28") (pintype "passive"))
      (node (ref "U1") (pin "20") (pinfunction "IO15_20") (pintype "bidirectional"))
      (node (ref "U6") (pin "4") (pinfunction "3D_4") (pintype "input"))
    )
    (net (code "156") (name "D3") (class "Default")
      (node (ref "BUS") (pin "27") (pinfunction "S_27") (pintype "passive"))
      (node (ref "U1") (pin "21") (pinfunction "IO16_21") (pintype "bidirectional"))
      (node (ref "U6") (pin "5") (pinfunction "4D_5") (pintype "input"))
    )
    (net (code "157") (name "D4") (class "Default")
      (node (ref "BUS") (pin "26") (pinfunction "S_26") (pintype "passive"))
      (node (ref "U1") (pin "24") (pinfunction "IO32_24") (pintype "bidirectional"))
      (node (ref "U6") (pin "6") (pinfunction "5D_6") (pintype "input"))
    )
    (net (code "158") (name "D5") (class "Default")
      (node (ref "BUS") (pin "25") (pinfunction "S_25") (pintype "passive"))
      (node (ref "U1") (pin "25") (pinfunction "IO31_25") (pintype "bidirectional"))
      (node (ref "U6") (pin "7") (pinfunction "6D_7") (pintype "input"))
    )
    (net (code "159") (name "D6") (class "Default")
      (node (ref "BUS") (pin "24") (pinfunction "S_24") (pintype "passive"))
      (node (ref "U1") (pin "26") (pinfunction "IO30_26") (pintype "bidirectional"))
      (node (ref "U6") (pin "8") (pinfunction "7D_8") (pintype "input"))
    )
    (net (code "160") (name "D7") (class "Default")
      (node (ref "BUS") (pin "23") (pinfunction "S_23") (pintype "passive"))
      (node (ref "U1") (pin "27") (pinfunction "IO29_27") (pintype "bidirectional"))
      (node (ref "U6") (pin "9") (pinfunction "8D_9") (pintype "input"))
    )
    (net (code "161") (name "GND") (class "Default")
      (node (ref "BUS") (pin "1") (pinfunction "S_1") (pintype "passive"))
      (node (ref "BUS") (pin "3") (pinfunction "S_3") (pintype "passive"))
      (node (ref "BUS") (pin "31") (pinfunction "S_31") (pintype "passive"))
      (node (ref "BUS") (pin "32") (pinfunction "S_32") (pintype "passive"))
      (node (ref "C1") (pin "-") (pinfunction "-_-") (pintype "passive"))
      (node (ref "C10") (pin "2") (pinfunction "2_2") (pintype "passive"))
      (node (ref "C11") (pin "2") (pinfunction "2_2") (pintype "passive"))
      (node (ref "C12") (pin "2") (pinfunction "2_2") (pintype "passive"))
      (node (ref "C13") (pin "2") (pinfunction "2_2") (pintype "passive"))
      (node (ref "C14") (pin "2") (pinfunction "2_2") (pintype "passive"))
      (node (ref "C15") (pin "2") (pinfunction "2_2") (pintype "passive"))
      (node (ref "C16") (pin "2") (pinfunction "2_2") (pintype "passive"))
      (node (ref "C17") (pin "2") (pinfunction "2_2") (pintype "passive"))
      (node (ref "C18") (pin "2") (pinfunction "2_2") (pintype "passive"))
      (node (ref "C19") (pin "2") (pinfunction "2_2") (pintype "passive"))
      (node (ref "C2") (pin "2") (pinfunction "2_2") (pintype "passive"))
      (node (ref "C20") (pin "2") (pinfunction "2_2") (pintype "passive"))
      (node (ref "C21") (pin "2") (pinfunction "2_2") (pintype "passive"))
      (node (ref "C22") (pin "2") (pinfunction "2_2") (pintype "passive"))
      (node (ref "C23") (pin "2") (pinfunction "2_2") (pintype "passive"))
      (node (ref "C24") (pin "2") (pinfunction "2_2") (pintype "passive"))
      (node (ref "C25") (pin "2") (pinfunction "2_2") (pintype "passive"))
      (node (ref "C26") (pin "2") (pinfunction "2_2") (pintype "passive"))
      (node (ref "C27") (pin "2") (pinfunction "2_2") (pintype "passive"))
      (node (ref "C28") (pin "2") (pinfunction "2_2") (pintype "passive"))
      (node (ref "C3") (pin "2") (pinfunction "2_2") (pintype "passive"))
      (node (ref "C4") (pin "2") (pinfunction "2_2") (pintype "passive"))
      (node (ref "C5") (pin "2") (pinfunction "2_2") (pintype "passive"))
      (node (ref "C6") (pin "2") (pinfunction "2_2") (pintype "passive"))
      (node (ref "C7") (pin "2") (pinfunction "2_2") (pintype "passive"))
      (node (ref "C8") (pin "2") (pinfunction "2_2") (pintype "passive"))
      (node (ref "C9") (pin "2") (pinfunction "2_2") (pintype "passive"))
      (node (ref "R1") (pin "1") (pinfunction "1_1") (pintype "passive"))
      (node (ref "R10") (pin "1") (pinfunction "1_1") (pintype "passive"))
      (node (ref "R11") (pin "1") (pinfunction "1_1") (pintype "passive"))
      (node (ref "R12") (pin "1") (pinfunction "1_1") (pintype "passive"))
      (node (ref "R13") (pin "1") (pinfunction "1_1") (pintype "passive"))
      (node (ref "R14") (pin "1") (pinfunction "1_1") (pintype "passive"))
      (node (ref "R15") (pin "1") (pinfunction "1_1") (pintype "passive"))
      (node (ref "R16") (pin "1") (pinfunction "1_1") (pintype "passive"))
      (node (ref "R17") (pin "1") (pinfunction "1_1") (pintype "passive"))
      (node (ref "R18") (pin "1") (pinfunction "1_1") (pintype "passive"))
      (node (ref "R21") (pin "1") (pinfunction "1_1") (pintype "passive"))
      (node (ref "R3") (pin "1") (pinfunction "1_1") (pintype "passive"))
      (node (ref "R4") (pin "1") (pinfunction "1_1") (pintype "passive"))
      (node (ref "R5") (pin "1") (pinfunction "1_1") (pintype "passive"))
      (node (ref "R6") (pin "1") (pinfunction "1_1") (pintype "passive"))
      (node (ref "R7") (pin "1") (pinfunction "1_1") (pintype "passive"))
      (node (ref "R8") (pin "1") (pinfunction "1_1") (pintype "passive"))
      (node (ref "R9") (pin "1") (pinfunction "1_1") (pintype "passive"))
      (node (ref "SV4") (pin "37") (pinfunction "S_37") (pintype "passive"))
      (node (ref "SV4") (pin "39") (pinfunction "S_39") (pintype "passive"))
      (node (ref "SV5") (pin "10") (pinfunction "S_10") (pintype "passive"))
      (node (ref "SV5") (pin "2") (pinfunction "S_2") (pintype "passive"))
      (node (ref "U1") (pin "10") (pinfunction "GND_10") (pintype "power_in"))
      (node (ref "U1") (pin "22") (pinfunction "GND_22") (pintype "power_in"))
      (node (ref "U1") (pin "30") (pinfunction "GND_30") (pintype "power_in"))
      (node (ref "U1") (pin "42") (pinfunction "GND_42") (pintype "power_in"))
      (node (ref "U10") (pin "1") (pinfunction "GND_1") (pintype "power_in"))
      (node (ref "U10") (pin "13") (pinfunction "~{OE}_13") (pintype "input"))
      (node (ref "U11") (pin "1") (pinfunction "GND_1") (pintype "power_in"))
      (node (ref "U11") (pin "13") (pinfunction "~{OE}_13") (pintype "input"))
      (node (ref "U12") (pin "1") (pinfunction "GND_1") (pintype "power_in"))
      (node (ref "U12") (pin "13") (pinfunction "~{OE}_13") (pintype "input"))
      (node (ref "U13") (pin "1") (pinfunction "GND_1") (pintype "power_in"))
      (node (ref "U13") (pin "13") (pinfunction "~{OE}_13") (pintype "input"))
      (node (ref "U14") (pin "1") (pinfunction "GND_1") (pintype "power_in"))
      (node (ref "U14") (pin "13") (pinfunction "~{OE}_13") (pintype "input"))
      (node (ref "U15") (pin "1") (pinfunction "GND_1") (pintype "power_in"))
      (node (ref "U15") (pin "13") (pinfunction "~{OE}_13") (pintype "input"))
      (node (ref "U16") (pin "1") (pinfunction "GND_1") (pintype "power_in"))
      (node (ref "U16") (pin "13") (pinfunction "~{OE}_13") (pintype "input"))
      (node (ref "U17") (pin "1") (pinfunction "GND_1") (pintype "power_in"))
      (node (ref "U17") (pin "13") (pinfunction "~{OE}_13") (pintype "input"))
      (node (ref "U18") (pin "1") (pinfunction "GND_1") (pintype "power_in"))
      (node (ref "U18") (pin "13") (pinfunction "~{OE}_13") (pintype "input"))
      (node (ref "U19") (pin "1") (pinfunction "GND_1") (pintype "power_in"))
      (node (ref "U19") (pin "13") (pinfunction "~{OE}_13") (pintype "input"))
      (node (ref "U2") (pin "10") (pinfunction "GND_10") (pintype "power_in"))
      (node (ref "U2") (pin "12") (pinfunction "Q4_12") (pintype "input"))
      (node (ref "U2") (pin "16") (pinfunction "Q6_16") (pintype "input"))
      (node (ref "U2") (pin "18") (pinfunction "Q7_18") (pintype "input"))
      (node (ref "U2") (pin "3") (pinfunction "Q0_3") (pintype "input"))
      (node (ref "U2") (pin "5") (pinfunction "Q1_5") (pintype "input"))
      (node (ref "U2") (pin "7") (pinfunction "Q2_7") (pintype "input"))
      (node (ref "U2") (pin "9") (pinfunction "Q3_9") (pintype "input"))
      (node (ref "U20") (pin "1") (pinfunction "GND_1") (pintype "power_in"))
      (node (ref "U20") (pin "13") (pinfunction "~{OE}_13") (pintype "input"))
      (node (ref "U21") (pin "1") (pinfunction "GND_1") (pintype "power_in"))
      (node (ref "U21") (pin "13") (pinfunction "~{OE}_13") (pintype "input"))
      (node (ref "U22") (pin "1") (pinfunction "GND_1") (pintype "power_in"))
      (node (ref "U22") (pin "13") (pinfunction "~{OE}_13") (pintype "input"))
      (node (ref "U23") (pin "1") (pinfunction "GND_1") (pintype "power_in"))
      (node (ref "U23") (pin "13") (pinfunction "~{OE}_13") (pintype "input"))
      (node (ref "U24") (pin "1") (pinfunction "GND_1") (pintype "power_in"))
      (node (ref "U24") (pin "13") (pinfunction "~{OE}_13") (pintype "input"))
      (node (ref "U3") (pin "10") (pinfunction "GND_10") (pintype "power_in"))
      (node (ref "U3") (pin "12") (pinfunction "Q4_12") (pintype "input"))
      (node (ref "U3") (pin "16") (pinfunction "Q6_16") (pintype "input"))
      (node (ref "U3") (pin "18") (pinfunction "Q7_18") (pintype "input"))
      (node (ref "U3") (pin "5") (pinfunction "Q1_5") (pintype "input"))
      (node (ref "U3") (pin "7") (pinfunction "Q2_7") (pintype "input"))
      (node (ref "U3") (pin "9") (pinfunction "Q3_9") (pintype "input"))
      (node (ref "U4") (pin "10") (pinfunction "I1_10") (pintype "input"))
      (node (ref "U4") (pin "12") (pinfunction "I0_12") (pintype "input"))
      (node (ref "U4") (pin "13") (pinfunction "I1_13") (pintype "input"))
      (node (ref "U4") (pin "5") (pinfunction "I1_5") (pintype "input"))
      (node (ref "U4") (pin "7") (pinfunction "GND_7") (pintype "power_in"))
      (node (ref "U5") (pin "10") (pinfunction "I1_10") (pintype "input"))
      (node (ref "U5") (pin "12") (pinfunction "I0_12") (pintype "input"))
      (node (ref "U5") (pin "13") (pinfunction "I1_13") (pintype "input"))
      (node (ref "U5") (pin "4") (pinfunction "I0_4") (pintype "input"))
      (node (ref "U5") (pin "5") (pinfunction "I1_5") (pintype "input"))
      (node (ref "U5") (pin "7") (pinfunction "GND_7") (pintype "power_in"))
      (node (ref "U5") (pin "9") (pinfunction "I0_9") (pintype "input"))
      (node (ref "U6") (pin "1") (pinfunction "OC_1") (pintype "input"))
      (node (ref "U6") (pin "10") (pinfunction "GND_10") (pintype "power_in"))
      (node (ref "U7") (pin "3") (pinfunction "C_3") (pintype "input"))
      (node (ref "U7") (pin "4") (pinfunction "G2A_4") (pintype "input"))
      (node (ref "U7") (pin "5") (pinfunction "G2B_5") (pintype "input"))
      (node (ref "U7") (pin "8") (pinfunction "GND_8") (pintype "power_in"))
      (node (ref "U8") (pin "1") (pinfunction "GND_1") (pintype "power_in"))
      (node (ref "U8") (pin "13") (pinfunction "~{OE}_13") (pintype "input"))
      (node (ref "U9") (pin "1") (pinfunction "GND_1") (pintype "power_in"))
      (node (ref "U9") (pin "13") (pinfunction "~{OE}_13") (pintype "input"))
    )
    (net (code "162") (name "Net-(SV4AB-S)") (class "Default")
      (node (ref "SV4") (pin "34") (pinfunction "S_34") (pintype "passive"))
      (node (ref "U7") (pin "14") (pinfunction "Y1_14") (pintype "output"))
    )
    (net (code "163") (name "Net-(SV4AC-S)") (class "Default")
      (node (ref "SV4") (pin "35") (pinfunction "S_35") (pintype "passive"))
      (node (ref "U7") (pin "13") (pinfunction "Y2_13") (pintype "output"))
    )
    (net (code "164") (name "Net-(SV4AD-S)") (class "Default")
      (node (ref "SV4") (pin "36") (pinfunction "S_36") (pintype "passive"))
      (node (ref "U7") (pin "12") (pinfunction "Y3_12") (pintype "output"))
    )
    (net (code "165") (name "Net-(U2A-G)") (class "Default")
      (node (ref "U2") (pin "1") (pinfunction "G_1") (pintype "input"))
      (node (ref "U3") (pin "1") (pinfunction "G_1") (pintype "input"))
      (node (ref "U4") (pin "3") (pinfunction "O_3") (pintype "output"))
    )
    (net (code "166") (name "Net-(U6A-1Q)") (class "Default")
      (node (ref "U6") (pin "19") (pinfunction "1Q_19") (pintype "tri_state"))
      (node (ref "U7") (pin "1") (pinfunction "A_1") (pintype "input"))
    )
    (net (code "167") (name "Net-(U6A-2Q)") (class "Default")
      (node (ref "U6") (pin "18") (pinfunction "2Q_18") (pintype "tri_state"))
      (node (ref "U7") (pin "2") (pinfunction "B_2") (pintype "input"))
    )
    (net (code "168") (name "Net-(U8A-R-EXT)") (class "Default")
      (node (ref "R1") (pin "2") (pinfunction "2_2") (pintype "passive"))
      (node (ref "U8") (pin "15") (pinfunction "R-EXT_15") (pintype "input"))
    )
    (net (code "169") (name "Net-(U8A-SDO)") (class "Default")
      (node (ref "U8") (pin "14") (pinfunction "SDO_14") (pintype "output"))
      (node (ref "U9") (pin "2") (pinfunction "SDI_2") (pintype "input"))
    )
    (net (code "170") (name "Net-(U9A-R-EXT)") (class "Default")
      (node (ref "R3") (pin "2") (pinfunction "2_2") (pintype "passive"))
      (node (ref "U9") (pin "15") (pinfunction "R-EXT_15") (pintype "input"))
    )
    (net (code "171") (name "Net-(U10A-LE)") (class "Default")
      (node (ref "U10") (pin "4") (pinfunction "LE_4") (pintype "input"))
      (node (ref "U11") (pin "4") (pinfunction "LE_4") (pintype "input"))
      (node (ref "U12") (pin "4") (pinfunction "LE_4") (pintype "input"))
      (node (ref "U13") (pin "4") (pinfunction "LE_4") (pintype "input"))
      (node (ref "U14") (pin "4") (pinfunction "LE_4") (pintype "input"))
      (node (ref "U15") (pin "4") (pinfunction "LE_4") (pintype "input"))
      (node (ref "U16") (pin "4") (pinfunction "LE_4") (pintype "input"))
      (node (ref "U17") (pin "4") (pinfunction "LE_4") (pintype "input"))
      (node (ref "U18") (pin "4") (pinfunction "LE_4") (pintype "input"))
      (node (ref "U19") (pin "4") (pinfunction "LE_4") (pintype "input"))
      (node (ref "U20") (pin "4") (pinfunction "LE_4") (pintype "input"))
      (node (ref "U21") (pin "4") (pinfunction "LE_4") (pintype "input"))
      (node (ref "U22") (pin "4") (pinfunction "LE_4") (pintype "input"))
      (node (ref "U23") (pin "4") (pinfunction "LE_4") (pintype "input"))
      (node (ref "U24") (pin "4") (pinfunction "LE_4") (pintype "input"))
      (node (ref "U4") (pin "8") (pinfunction "O_8") (pintype "output"))
      (node (ref "U8") (pin "4") (pinfunction "LE_4") (pintype "input"))
      (node (ref "U9") (pin "4") (pinfunction "LE_4") (pintype "input"))
    )
    (net (code "172") (name "Net-(U10A-R-EXT)") (class "Default")
      (node (ref "R4") (pin "2") (pinfunction "2_2") (pintype "passive"))
      (node (ref "U10") (pin "15") (pinfunction "R-EXT_15") (pintype "input"))
    )
    (net (code "173") (name "Net-(U10A-SDI)") (class "Default")
      (node (ref "U10") (pin "2") (pinfunction "SDI_2") (pintype "input"))
      (node (ref "U9") (pin "14") (pinfunction "SDO_14") (pintype "output"))
    )
    (net (code "174") (name "Net-(U10A-SDO)") (class "Default")
      (node (ref "U10") (pin "14") (pinfunction "SDO_14") (pintype "output"))
      (node (ref "U11") (pin "2") (pinfunction "SDI_2") (pintype "input"))
    )
    (net (code "175") (name "Net-(U11A-R-EXT)") (class "Default")
      (node (ref "R5") (pin "2") (pinfunction "2_2") (pintype "passive"))
      (node (ref "U11") (pin "15") (pinfunction "R-EXT_15") (pintype "input"))
    )
    (net (code "176") (name "Net-(U11A-SDO)") (class "Default")
      (node (ref "U11") (pin "14") (pinfunction "SDO_14") (pintype "output"))
      (node (ref "U12") (pin "2") (pinfunction "SDI_2") (pintype "input"))
    )
    (net (code "177") (name "Net-(U12A-R-EXT)") (class "Default")
      (node (ref "R6") (pin "2") (pinfunction "2_2") (pintype "passive"))
      (node (ref "U12") (pin "15") (pinfunction "R-EXT_15") (pintype "input"))
    )
    (net (code "178") (name "Net-(U12A-SDO)") (class "Default")
      (node (ref "U12") (pin "14") (pinfunction "SDO_14") (pintype "output"))
      (node (ref "U13") (pin "2") (pinfunction "SDI_2") (pintype "input"))
    )
    (net (code "179") (name "Net-(U13A-R-EXT)") (class "Default")
      (node (ref "R7") (pin "2") (pinfunction "2_2") (pintype "passive"))
      (node (ref "U13") (pin "15") (pinfunction "R-EXT_15") (pintype "input"))
    )
    (net (code "180") (name "Net-(U13A-SDO)") (class "Default")
      (node (ref "U13") (pin "14") (pinfunction "SDO_14") (pintype "output"))
      (node (ref "U14") (pin "2") (pinfunction "SDI_2") (pintype "input"))
    )
    (net (code "181") (name "Net-(U14A-R-EXT)") (class "Default")
      (node (ref "R8") (pin "2") (pinfunction "2_2") (pintype "passive"))
      (node (ref "U14") (pin "15") (pinfunction "R-EXT_15") (pintype "input"))
    )
    (net (code "182") (name "Net-(U14A-SDO)") (class "Default")
      (node (ref "U14") (pin "14") (pinfunction "SDO_14") (pintype "output"))
      (node (ref "U15") (pin "2") (pinfunction "SDI_2") (pintype "input"))
    )
    (net (code "183") (name "Net-(U15A-R-EXT)") (class "Default")
      (node (ref "R9") (pin "2") (pinfunction "2_2") (pintype "passive"))
      (node (ref "U15") (pin "15") (pinfunction "R-EXT_15") (pintype "input"))
    )
    (net (code "184") (name "Net-(U15A-SDO)") (class "Default")
      (node (ref "U15") (pin "14") (pinfunction "SDO_14") (pintype "output"))
      (node (ref "U16") (pin "2") (pinfunction "SDI_2") (pintype "input"))
    )
    (net (code "185") (name "Net-(U16A-R-EXT)") (class "Default")
      (node (ref "R10") (pin "2") (pinfunction "2_2") (pintype "passive"))
      (node (ref "U16") (pin "15") (pinfunction "R-EXT_15") (pintype "input"))
    )
    (net (code "186") (name "Net-(U16A-SDO)") (class "Default")
      (node (ref "U16") (pin "14") (pinfunction "SDO_14") (pintype "output"))
      (node (ref "U17") (pin "2") (pinfunction "SDI_2") (pintype "input"))
    )
    (net (code "187") (name "Net-(U17A-R-EXT)") (class "Default")
      (node (ref "R11") (pin "2") (pinfunction "2_2") (pintype "passive"))
      (node (ref "U17") (pin "15") (pinfunction "R-EXT_15") (pintype "input"))
    )
    (net (code "188") (name "Net-(U17A-SDO)") (class "Default")
      (node (ref "U17") (pin "14") (pinfunction "SDO_14") (pintype "output"))
      (node (ref "U18") (pin "2") (pinfunction "SDI_2") (pintype "input"))
    )
    (net (code "189") (name "Net-(U18A-R-EXT)") (class "Default")
      (node (ref "R12") (pin "2") (pinfunction "2_2") (pintype "passive"))
      (node (ref "U18") (pin "15") (pinfunction "R-EXT_15") (pintype "input"))
    )
    (net (code "190") (name "Net-(U18A-SDO)") (class "Default")
      (node (ref "U18") (pin "14") (pinfunction "SDO_14") (pintype "output"))
      (node (ref "U19") (pin "2") (pinfunction "SDI_2") (pintype "input"))
    )
    (net (code "191") (name "Net-(U19A-R-EXT)") (class "Default")
      (node (ref "R13") (pin "2") (pinfunction "2_2") (pintype "passive"))
      (node (ref "U19") (pin "15") (pinfunction "R-EXT_15") (pintype "input"))
    )
    (net (code "192") (name "Net-(U19A-SDO)") (class "Default")
      (node (ref "U19") (pin "14") (pinfunction "SDO_14") (pintype "output"))
      (node (ref "U20") (pin "2") (pinfunction "SDI_2") (pintype "input"))
    )
    (net (code "193") (name "Net-(U20A-R-EXT)") (class "Default")
      (node (ref "R14") (pin "2") (pinfunction "2_2") (pintype "passive"))
      (node (ref "U20") (pin "15") (pinfunction "R-EXT_15") (pintype "input"))
    )
    (net (code "194") (name "Net-(U20A-SDO)") (class "Default")
      (node (ref "U20") (pin "14") (pinfunction "SDO_14") (pintype "output"))
      (node (ref "U21") (pin "2") (pinfunction "SDI_2") (pintype "input"))
    )
    (net (code "195") (name "Net-(U21A-R-EXT)") (class "Default")
      (node (ref "R15") (pin "2") (pinfunction "2_2") (pintype "passive"))
      (node (ref "U21") (pin "15") (pinfunction "R-EXT_15") (pintype "input"))
    )
    (net (code "196") (name "Net-(U21A-SDO)") (class "Default")
      (node (ref "U21") (pin "14") (pinfunction "SDO_14") (pintype "output"))
      (node (ref "U22") (pin "2") (pinfunction "SDI_2") (pintype "input"))
    )
    (net (code "197") (name "Net-(U22A-R-EXT)") (class "Default")
      (node (ref "R16") (pin "2") (pinfunction "2_2") (pintype "passive"))
      (node (ref "U22") (pin "15") (pinfunction "R-EXT_15") (pintype "input"))
    )
    (net (code "198") (name "Net-(U22A-SDO)") (class "Default")
      (node (ref "U22") (pin "14") (pinfunction "SDO_14") (pintype "output"))
      (node (ref "U23") (pin "2") (pinfunction "SDI_2") (pintype "input"))
    )
    (net (code "199") (name "Net-(U23A-R-EXT)") (class "Default")
      (node (ref "R17") (pin "2") (pinfunction "2_2") (pintype "passive"))
      (node (ref "U23") (pin "15") (pinfunction "R-EXT_15") (pintype "input"))
    )
    (net (code "200") (name "Net-(U23A-SDO)") (class "Default")
      (node (ref "U23") (pin "14") (pinfunction "SDO_14") (pintype "output"))
      (node (ref "U24") (pin "2") (pinfunction "SDI_2") (pintype "input"))
    )
    (net (code "201") (name "Net-(U24A-R-EXT)") (class "Default")
      (node (ref "R18") (pin "2") (pinfunction "2_2") (pintype "passive"))
      (node (ref "U24") (pin "15") (pinfunction "R-EXT_15") (pintype "input"))
    )
    (net (code "202") (name "SCK") (class "Default")
      (node (ref "U1") (pin "5") (pinfunction "IO2_5") (pintype "bidirectional"))
      (node (ref "U4") (pin "4") (pinfunction "I0_4") (pintype "input"))
    )
    (net (code "203") (name "SDO") (class "Default")
      (node (ref "U1") (pin "4") (pinfunction "IO1_4") (pintype "bidirectional"))
      (node (ref "U8") (pin "2") (pinfunction "SDI_2") (pintype "input"))
    )
    (net (code "204") (name "TCK") (class "Default")
      (node (ref "R21") (pin "2") (pinfunction "2_2") (pintype "passive"))
      (node (ref "SV5") (pin "1") (pinfunction "S_1") (pintype "passive"))
      (node (ref "U1") (pin "32") (pinfunction "IO20/TCK_32") (pintype "bidirectional"))
    )
    (net (code "205") (name "TDI") (class "Default")
      (node (ref "R20") (pin "1") (pinfunction "1_1") (pintype "passive"))
      (node (ref "SV5") (pin "9") (pinfunction "S_9") (pintype "passive"))
      (node (ref "U1") (pin "7") (pinfunction "IO4/TDI_7") (pintype "bidirectional"))
    )
    (net (code "206") (name "TDO") (class "Default")
      (node (ref "SV5") (pin "3") (pinfunction "S_3") (pintype "passive"))
      (node (ref "U1") (pin "38") (pinfunction "IO25/TDO_38") (pintype "bidirectional"))
    )
    (net (code "207") (name "TMS") (class "Default")
      (node (ref "R19") (pin "1") (pinfunction "1_1") (pintype "passive"))
      (node (ref "SV5") (pin "5") (pinfunction "S_5") (pintype "passive"))
      (node (ref "U1") (pin "13") (pinfunction "IO9/TMS_13") (pintype "bidirectional"))
    )
    (net (code "208") (name "unconnected-(BUSAM-S-Pad8)") (class "Default")
      (node (ref "BUS") (pin "8") (pinfunction "S_8") (pintype "passive"))
    )
    (net (code "209") (name "unconnected-(BUSB-S-Pad10)") (class "Default")
      (node (ref "BUS") (pin "10") (pinfunction "S_10") (pintype "passive"))
    )
    (net (code "210") (name "unconnected-(BUSC-S-Pad11)") (class "Default")
      (node (ref "BUS") (pin "11") (pinfunction "S_11") (pintype "passive"))
    )
    (net (code "211") (name "unconnected-(BUSD-S-Pad12)") (class "Default")
      (node (ref "BUS") (pin "12") (pinfunction "S_12") (pintype "passive"))
    )
    (net (code "212") (name "unconnected-(BUSE-S-Pad13)") (class "Default")
      (node (ref "BUS") (pin "13") (pinfunction "S_13") (pintype "passive"))
    )
    (net (code "213") (name "unconnected-(BUSF-S-Pad14)") (class "Default")
      (node (ref "BUS") (pin "14") (pinfunction "S_14") (pintype "passive"))
    )
    (net (code "214") (name "unconnected-(BUSG-S-Pad15)") (class "Default")
      (node (ref "BUS") (pin "15") (pinfunction "S_15") (pintype "passive"))
    )
    (net (code "215") (name "unconnected-(BUSH-S-Pad16)") (class "Default")
      (node (ref "BUS") (pin "16") (pinfunction "S_16") (pintype "passive"))
    )
    (net (code "216") (name "unconnected-(BUSI-S-Pad17)") (class "Default")
      (node (ref "BUS") (pin "17") (pinfunction "S_17") (pintype "passive"))
    )
    (net (code "217") (name "unconnected-(BUSJ-S-Pad18)") (class "Default")
      (node (ref "BUS") (pin "18") (pinfunction "S_18") (pintype "passive"))
    )
    (net (code "218") (name "unconnected-(BUSK-S-Pad19)") (class "Default")
      (node (ref "BUS") (pin "19") (pinfunction "S_19") (pintype "passive"))
    )
    (net (code "219") (name "unconnected-(BUSM-S-Pad20)") (class "Default")
      (node (ref "BUS") (pin "20") (pinfunction "S_20") (pintype "passive"))
    )
    (net (code "220") (name "unconnected-(BUSN-S-Pad21)") (class "Default")
      (node (ref "BUS") (pin "21") (pinfunction "S_21") (pintype "passive"))
    )
    (net (code "221") (name "unconnected-(BUSO-S-Pad22)") (class "Default")
      (node (ref "BUS") (pin "22") (pinfunction "S_22") (pintype "passive"))
    )
    (net (code "222") (name "unconnected-(SV3I-S-Pad17)") (class "Default")
      (node (ref "SV3") (pin "17") (pinfunction "S_17") (pintype "passive"))
    )
    (net (code "223") (name "unconnected-(SV3J-S-Pad18)") (class "Default")
      (node (ref "SV3") (pin "18") (pinfunction "S_18") (pintype "passive"))
    )
    (net (code "224") (name "unconnected-(SV3K-S-Pad19)") (class "Default")
      (node (ref "SV3") (pin "19") (pinfunction "S_19") (pintype "passive"))
    )
    (net (code "225") (name "unconnected-(SV3M-S-Pad20)") (class "Default")
      (node (ref "SV3") (pin "20") (pinfunction "S_20") (pintype "passive"))
    )
    (net (code "226") (name "unconnected-(SV3N-S-Pad21)") (class "Default")
      (node (ref "SV3") (pin "21") (pinfunction "S_21") (pintype "passive"))
    )
    (net (code "227") (name "unconnected-(SV3O-S-Pad22)") (class "Default")
      (node (ref "SV3") (pin "22") (pinfunction "S_22") (pintype "passive"))
    )
    (net (code "228") (name "unconnected-(SV3P-S-Pad23)") (class "Default")
      (node (ref "SV3") (pin "23") (pinfunction "S_23") (pintype "passive"))
    )
    (net (code "229") (name "unconnected-(SV3Q-S-Pad24)") (class "Default")
      (node (ref "SV3") (pin "24") (pinfunction "S_24") (pintype "passive"))
    )
    (net (code "230") (name "unconnected-(SV4AA-S-Pad33)") (class "Default")
      (node (ref "SV4") (pin "33") (pinfunction "S_33") (pintype "passive"))
    )
    (net (code "231") (name "unconnected-(SV4R-S-Pad25)") (class "Default")
      (node (ref "SV4") (pin "25") (pinfunction "S_25") (pintype "passive"))
    )
    (net (code "232") (name "unconnected-(SV4S-S-Pad26)") (class "Default")
      (node (ref "SV4") (pin "26") (pinfunction "S_26") (pintype "passive"))
    )
    (net (code "233") (name "unconnected-(SV4T-S-Pad27)") (class "Default")
      (node (ref "SV4") (pin "27") (pinfunction "S_27") (pintype "passive"))
    )
    (net (code "234") (name "unconnected-(SV4U-S-Pad28)") (class "Default")
      (node (ref "SV4") (pin "28") (pinfunction "S_28") (pintype "passive"))
    )
    (net (code "235") (name "unconnected-(SV4V-S-Pad29)") (class "Default")
      (node (ref "SV4") (pin "29") (pinfunction "S_29") (pintype "passive"))
    )
    (net (code "236") (name "unconnected-(SV4X-S-Pad30)") (class "Default")
      (node (ref "SV4") (pin "30") (pinfunction "S_30") (pintype "passive"))
    )
    (net (code "237") (name "unconnected-(SV4Y-S-Pad31)") (class "Default")
      (node (ref "SV4") (pin "31") (pinfunction "S_31") (pintype "passive"))
    )
    (net (code "238") (name "unconnected-(SV4Z-S-Pad32)") (class "Default")
      (node (ref "SV4") (pin "32") (pinfunction "S_32") (pintype "passive"))
    )
    (net (code "239") (name "unconnected-(SV5G-S-Pad6)") (class "Default")
      (node (ref "SV5") (pin "6") (pinfunction "S_6") (pintype "passive"))
    )
    (net (code "240") (name "unconnected-(SV5H-S-Pad7)") (class "Default")
      (node (ref "SV5") (pin "7") (pinfunction "S_7") (pintype "passive"))
    )
    (net (code "241") (name "unconnected-(SV5I-S-Pad8)") (class "Default")
      (node (ref "SV5") (pin "8") (pinfunction "S_8") (pintype "passive"))
    )
    (net (code "242") (name "unconnected-(U1B-IO5-Pad8)") (class "Default")
      (node (ref "U1") (pin "8") (pinfunction "IO5_8") (pintype "bidirectional"))
    )
    (net (code "243") (name "unconnected-(U1B-IO6-Pad9)") (class "Default")
      (node (ref "U1") (pin "9") (pinfunction "IO6_9") (pintype "bidirectional"))
    )
    (net (code "244") (name "unconnected-(U1B-IO7-Pad11)") (class "Default")
      (node (ref "U1") (pin "11") (pinfunction "IO7_11") (pintype "bidirectional"))
    )
    (net (code "245") (name "unconnected-(U1B-IO8-Pad12)") (class "Default")
      (node (ref "U1") (pin "12") (pinfunction "IO8_12") (pintype "bidirectional"))
    )
    (net (code "246") (name "unconnected-(U1B-IO10-Pad14)") (class "Default")
      (node (ref "U1") (pin "14") (pinfunction "IO10_14") (pintype "bidirectional"))
    )
    (net (code "247") (name "unconnected-(U1B-IO11-Pad16)") (class "Default")
      (node (ref "U1") (pin "16") (pinfunction "IO11_16") (pintype "bidirectional"))
    )
    (net (code "248") (name "unconnected-(U1B-IO12-Pad17)") (class "Default")
      (node (ref "U1") (pin "17") (pinfunction "IO12_17") (pintype "bidirectional"))
    )
    (net (code "249") (name "unconnected-(U1B-IO17-Pad41)") (class "Default")
      (node (ref "U1") (pin "41") (pinfunction "IO17_41") (pintype "bidirectional"))
    )
    (net (code "250") (name "unconnected-(U1B-IO18-Pad40)") (class "Default")
      (node (ref "U1") (pin "40") (pinfunction "IO18_40") (pintype "bidirectional"))
    )
    (net (code "251") (name "unconnected-(U1B-IO19-Pad39)") (class "Default")
      (node (ref "U1") (pin "39") (pinfunction "IO19_39") (pintype "bidirectional"))
    )
    (net (code "252") (name "unconnected-(U1B-IO21-Pad37)") (class "Default")
      (node (ref "U1") (pin "37") (pinfunction "IO21_37") (pintype "bidirectional"))
    )
    (net (code "253") (name "unconnected-(U1B-IO22-Pad36)") (class "Default")
      (node (ref "U1") (pin "36") (pinfunction "IO22_36") (pintype "bidirectional"))
    )
    (net (code "254") (name "unconnected-(U1B-IO23-Pad34)") (class "Default")
      (node (ref "U1") (pin "34") (pinfunction "IO23_34") (pintype "bidirectional"))
    )
    (net (code "255") (name "unconnected-(U1B-IO24-Pad33)") (class "Default")
      (node (ref "U1") (pin "33") (pinfunction "IO24_33") (pintype "bidirectional"))
    )
    (net (code "256") (name "unconnected-(U1B-IO26-Pad31)") (class "Default")
      (node (ref "U1") (pin "31") (pinfunction "IO26_31") (pintype "bidirectional"))
    )
    (net (code "257") (name "unconnected-(U1B-IO27-Pad29)") (class "Default")
      (node (ref "U1") (pin "29") (pinfunction "IO27_29") (pintype "bidirectional"))
    )
    (net (code "258") (name "unconnected-(U1B-IO28-Pad28)") (class "Default")
      (node (ref "U1") (pin "28") (pinfunction "IO28_28") (pintype "bidirectional"))
    )
    (net (code "259") (name "unconnected-(U1B-OE1-Pad44)") (class "Default")
      (node (ref "U1") (pin "44") (pinfunction "OE1_44") (pintype "input"))
    )
    (net (code "260") (name "unconnected-(U1B-OE2-GCLK2-Pad2)") (class "Default")
      (node (ref "U1") (pin "2") (pinfunction "OE2-GCLK2_2") (pintype "input"))
    )
    (net (code "261") (name "unconnected-(U4D-O-Pad11)") (class "Default")
      (node (ref "U4") (pin "11") (pinfunction "O_11") (pintype "output"))
    )
    (net (code "262") (name "unconnected-(U5B-O-Pad6)") (class "Default")
      (node (ref "U5") (pin "6") (pinfunction "O_6") (pintype "output"))
    )
    (net (code "263") (name "unconnected-(U5C-O-Pad8)") (class "Default")
      (node (ref "U5") (pin "8") (pinfunction "O_8") (pintype "output"))
    )
    (net (code "264") (name "unconnected-(U5D-O-Pad11)") (class "Default")
      (node (ref "U5") (pin "11") (pinfunction "O_11") (pintype "output"))
    )
    (net (code "265") (name "unconnected-(U6A-3Q-Pad17)") (class "Default")
      (node (ref "U6") (pin "17") (pinfunction "3Q_17") (pintype "tri_state"))
    )
    (net (code "266") (name "unconnected-(U6A-4Q-Pad16)") (class "Default")
      (node (ref "U6") (pin "16") (pinfunction "4Q_16") (pintype "tri_state"))
    )
    (net (code "267") (name "unconnected-(U6A-5Q-Pad15)") (class "Default")
      (node (ref "U6") (pin "15") (pinfunction "5Q_15") (pintype "tri_state"))
    )
    (net (code "268") (name "unconnected-(U6A-6Q-Pad14)") (class "Default")
      (node (ref "U6") (pin "14") (pinfunction "6Q_14") (pintype "tri_state"))
    )
    (net (code "269") (name "unconnected-(U6A-7Q-Pad13)") (class "Default")
      (node (ref "U6") (pin "13") (pinfunction "7Q_13") (pintype "tri_state"))
    )
    (net (code "270") (name "unconnected-(U6A-8Q-Pad12)") (class "Default")
      (node (ref "U6") (pin "12") (pinfunction "8Q_12") (pintype "tri_state"))
    )
    (net (code "271") (name "unconnected-(U7A-Y0-Pad15)") (class "Default")
      (node (ref "U7") (pin "15") (pinfunction "Y0_15") (pintype "output"))
    )
    (net (code "272") (name "unconnected-(U7A-Y4-Pad11)") (class "Default")
      (node (ref "U7") (pin "11") (pinfunction "Y4_11") (pintype "output"))
    )
    (net (code "273") (name "unconnected-(U7A-Y5-Pad10)") (class "Default")
      (node (ref "U7") (pin "10") (pinfunction "Y5_10") (pintype "output"))
    )
    (net (code "274") (name "unconnected-(U7A-Y6-Pad9)") (class "Default")
      (node (ref "U7") (pin "9") (pinfunction "Y6_9") (pintype "output"))
    )
    (net (code "275") (name "unconnected-(U7A-Y7-Pad7)") (class "Default")
      (node (ref "U7") (pin "7") (pinfunction "Y7_7") (pintype "output"))
    )
    (net (code "276") (name "unconnected-(U24A-SDO-Pad14)") (class "Default")
      (node (ref "U24") (pin "14") (pinfunction "SDO_14") (pintype "output"))
    )
  )
)
